# POVRotor.net
KiCad netlist of a schematic drawn in EAGLE
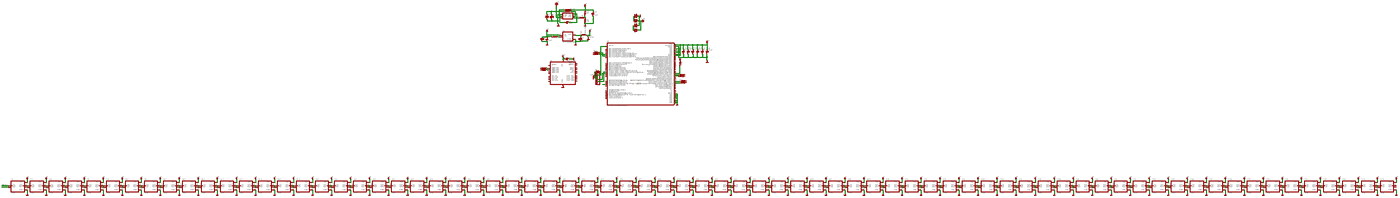
[diagram p0: schematic, sheet 1, overview]
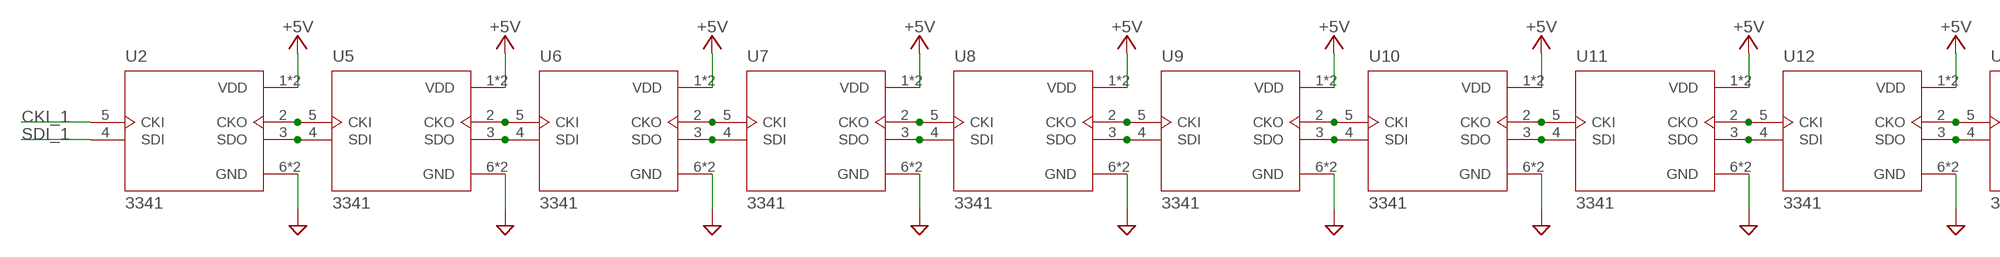
[diagram p1: schematic, sheet 1, part 1 of 8]
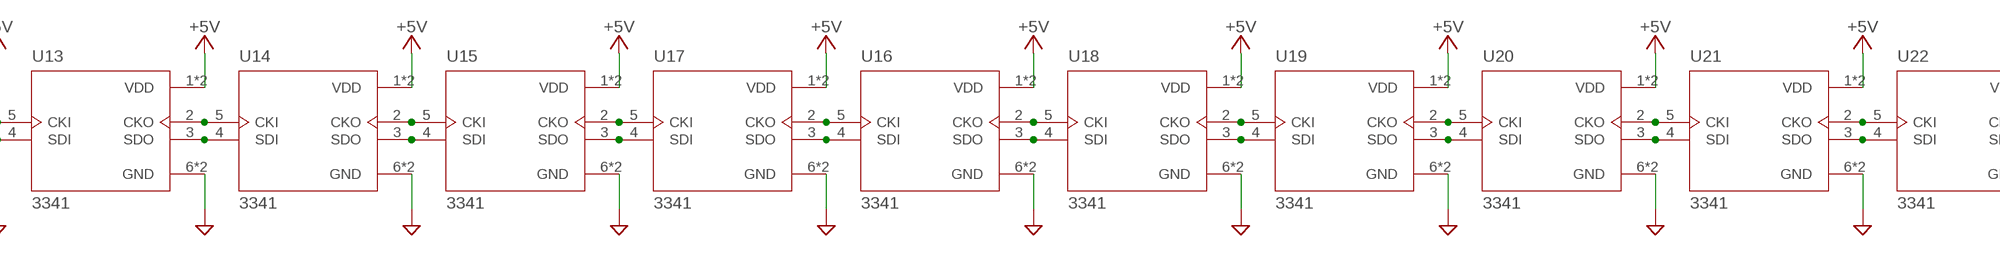
[diagram p2: schematic, sheet 1, part 2 of 8]
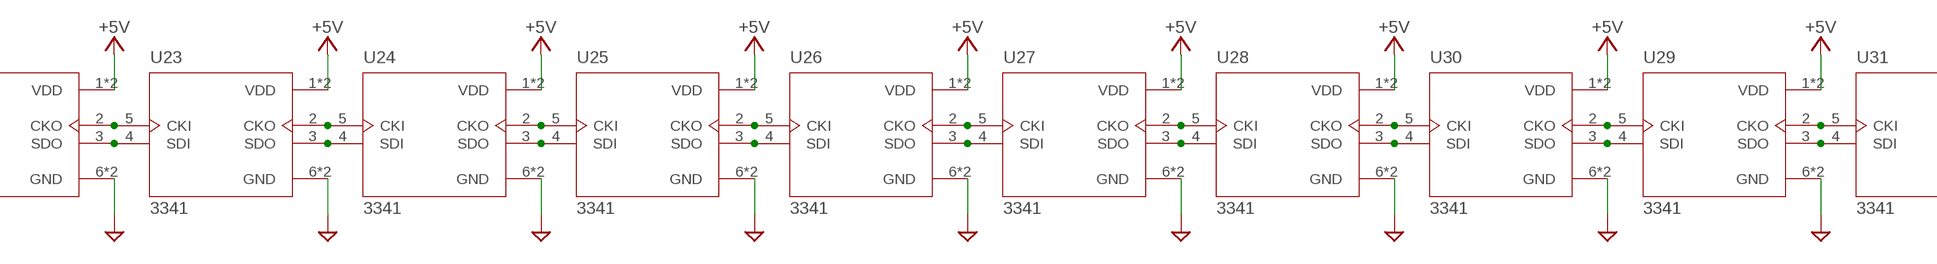
[diagram p3: schematic, sheet 1, part 3 of 8]
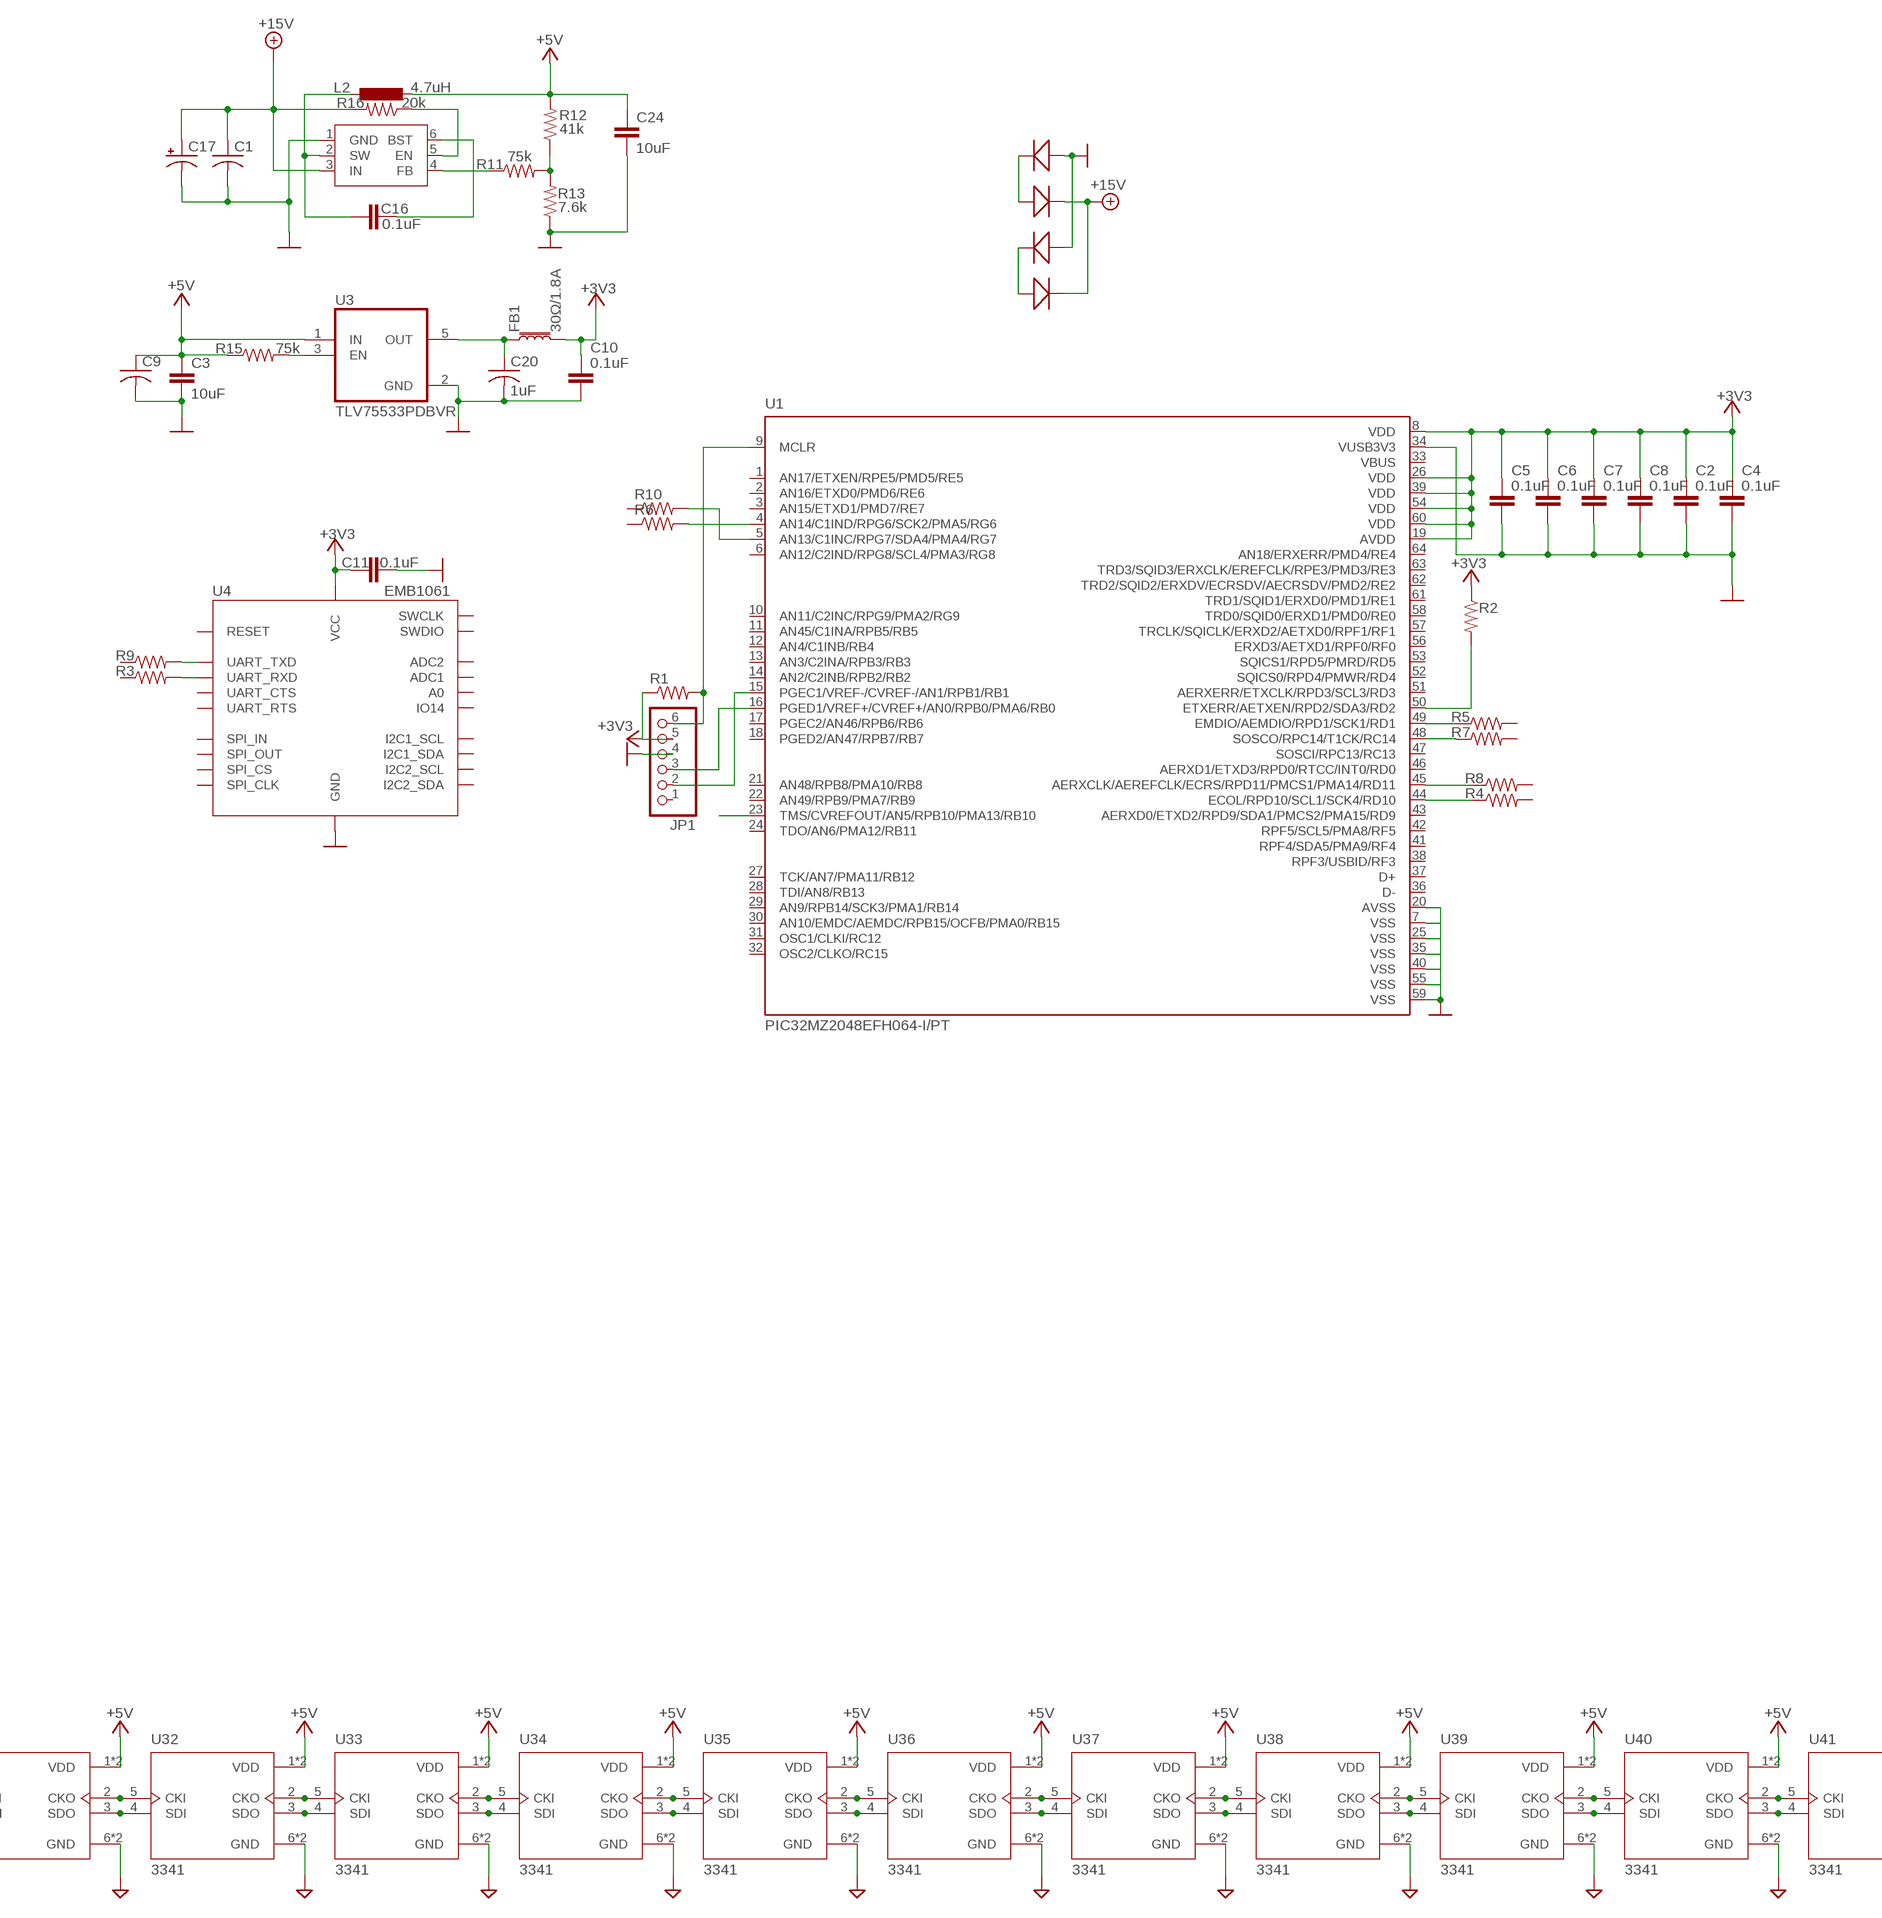
[diagram p4: schematic, sheet 1, part 4 of 8]
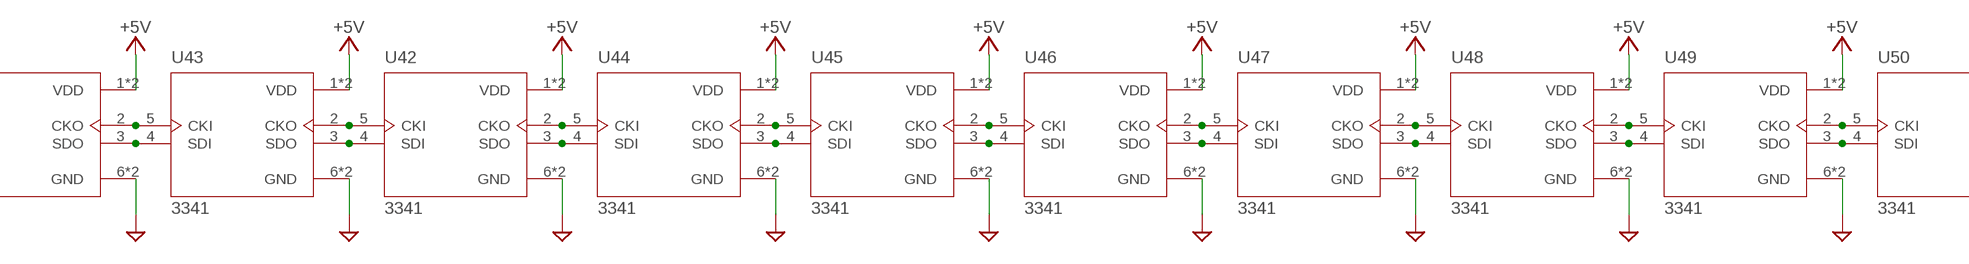
[diagram p5: schematic, sheet 1, part 5 of 8]
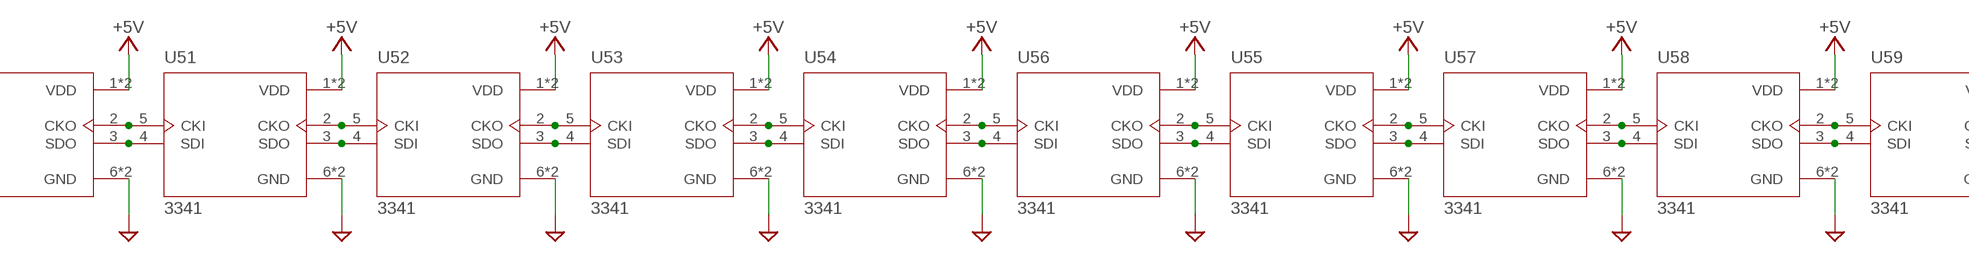
[diagram p6: schematic, sheet 1, part 6 of 8]
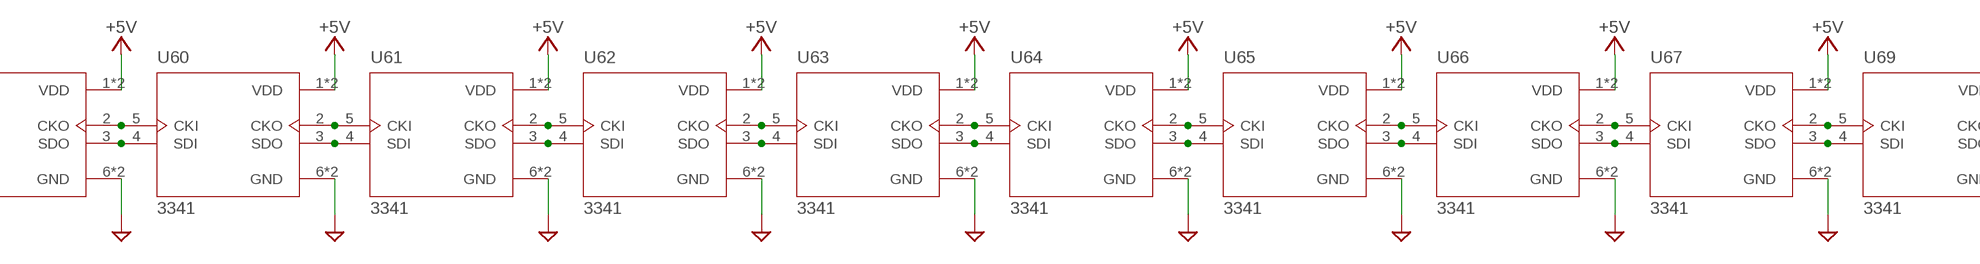
[diagram p7: schematic, sheet 1, part 7 of 8]
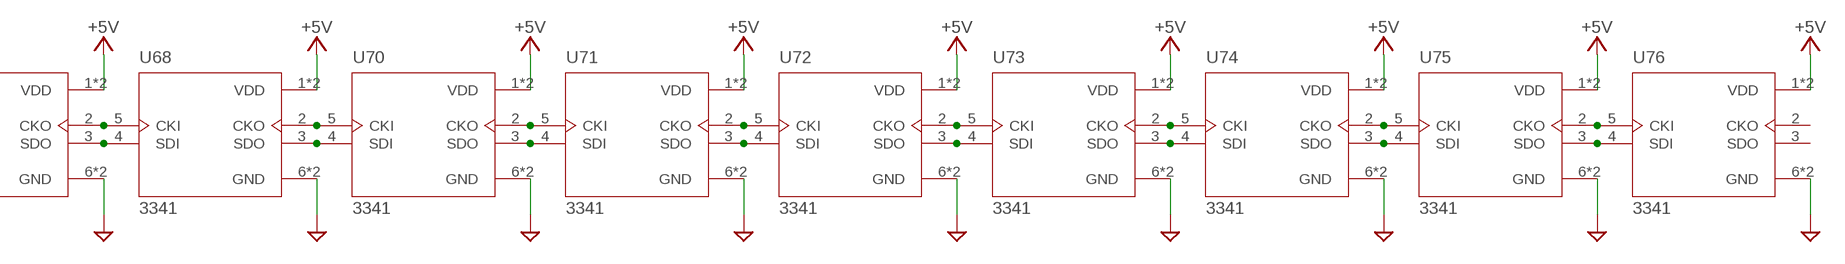
[diagram p8: schematic, sheet 1, part 8 of 8]

(export (version "E")
  (design (tool "Eeschema 10.0.6"))
  (components
    (comp (ref "C1")
      (value "C-USC0805")
      (footprint "eagle-import:C0805")
      (libsource (lib "eagle-import") (part "resistor_348_C-USC0805"))
    )
    (comp (ref "C2")
      (value "0.1uF")
      (footprint "eagle-import:C0603")
      (libsource (lib "eagle-import") (part "C-EUC0603"))
    )
    (comp (ref "C3")
      (value "10uF")
      (footprint "eagle-import:C1206")
      (libsource (lib "eagle-import") (part "C-EUC1206"))
    )
    (comp (ref "C4")
      (value "0.1uF")
      (footprint "eagle-import:C0603")
      (libsource (lib "eagle-import") (part "C-EUC0603"))
    )
    (comp (ref "C5")
      (value "0.1uF")
      (footprint "eagle-import:C0603")
      (libsource (lib "eagle-import") (part "C-EUC0603"))
    )
    (comp (ref "C6")
      (value "0.1uF")
      (footprint "eagle-import:C0603")
      (libsource (lib "eagle-import") (part "C-EUC0603"))
    )
    (comp (ref "C7")
      (value "0.1uF")
      (footprint "eagle-import:C0603")
      (libsource (lib "eagle-import") (part "C-EUC0603"))
    )
    (comp (ref "C8")
      (value "0.1uF")
      (footprint "eagle-import:C0603")
      (libsource (lib "eagle-import") (part "C-EUC0603"))
    )
    (comp (ref "C9")
      (value "C-USC0805")
      (footprint "eagle-import:C0805")
      (libsource (lib "eagle-import") (part "resistor_348_C-USC0805"))
    )
    (comp (ref "C10")
      (value "0.1uF")
      (footprint "eagle-import:C0603")
      (libsource (lib "eagle-import") (part "C-EUC0603"))
    )
    (comp (ref "C11")
      (value "0.1uF")
      (footprint "eagle-import:C0603")
      (libsource (lib "eagle-import") (part "C-EUC0603"))
    )
    (comp (ref "C16")
      (value "0.1uF")
      (footprint "eagle-import:C0603")
      (libsource (lib "eagle-import") (part "C-EUC0603"))
    )
    (comp (ref "C17")
      (value "CPOL-USC/6032-28R")
      (footprint "eagle-import:C_6032-28R")
      (libsource (lib "eagle-import") (part "CPOL-USC/6032-28R"))
    )
    (comp (ref "C20")
      (value "1uF")
      (footprint "eagle-import:C0805")
      (libsource (lib "eagle-import") (part "C-USC0805"))
    )
    (comp (ref "C24")
      (value "10uF")
      (footprint "eagle-import:C1206")
      (libsource (lib "eagle-import") (part "C-EUC1206"))
    )
    (comp (ref "D2")
      (value "SMD-DIODE-SCHOTTKY-40V-3A(DO-214AB)")
      (footprint "eagle-import:DO-214AB")
      (fields (field (name "MF") "Vishay") (field (name "MP") "SS34-E3/57T"))
      (libsource (lib "eagle-import") (part "SMD-DIODE-SCHOTTKY-40V-3A(DO-214AB)"))
    )
    (comp (ref "D3")
      (value "SMD-DIODE-SCHOTTKY-40V-3A(DO-214AB)")
      (footprint "eagle-import:DO-214AB")
      (fields (field (name "MF") "Vishay") (field (name "MP") "SS34-E3/57T"))
      (libsource (lib "eagle-import") (part "SMD-DIODE-SCHOTTKY-40V-3A(DO-214AB)"))
    )
    (comp (ref "D4")
      (value "SMD-DIODE-SCHOTTKY-40V-3A(DO-214AB)")
      (footprint "eagle-import:DO-214AB")
      (fields (field (name "MF") "Vishay") (field (name "MP") "SS34-E3/57T"))
      (libsource (lib "eagle-import") (part "SMD-DIODE-SCHOTTKY-40V-3A(DO-214AB)"))
    )
    (comp (ref "D5")
      (value "SMD-DIODE-SCHOTTKY-40V-3A(DO-214AB)")
      (footprint "eagle-import:DO-214AB")
      (fields (field (name "MF") "Vishay") (field (name "MP") "SS34-E3/57T"))
      (libsource (lib "eagle-import") (part "SMD-DIODE-SCHOTTKY-40V-3A(DO-214AB)"))
    )
    (comp (ref "FB1")
      (value "30Ω/1.8A")
      (footprint "eagle-import:0603")
      (libsource (lib "eagle-import") (part "FERRITE_BEAD-0603"))
    )
    (comp (ref "JP1")
      (value "PINHD-1X6/90")
      (footprint "eagle-import:1X06_90")
      (libsource (lib "eagle-import") (part "PINHD-1X6/90"))
    )
    (comp (ref "L2")
      (value "4.7uH")
      (footprint "eagle-import:L2825P")
      (libsource (lib "eagle-import") (part "L-EUL2825P"))
    )
    (comp (ref "R1")
      (value "R-US_R0603")
      (footprint "eagle-import:R0603")
      (libsource (lib "eagle-import") (part "resistor_348_R-US_R0603"))
    )
    (comp (ref "R2")
      (value "R-US_R0603")
      (footprint "eagle-import:R0603")
      (libsource (lib "eagle-import") (part "resistor_348_R-US_R0603"))
    )
    (comp (ref "R3")
      (value "R-US_R0603")
      (footprint "eagle-import:R0603")
      (libsource (lib "eagle-import") (part "resistor_348_R-US_R0603"))
    )
    (comp (ref "R4")
      (value "R-US_R0603")
      (footprint "eagle-import:R0603")
      (libsource (lib "eagle-import") (part "resistor_348_R-US_R0603"))
    )
    (comp (ref "R5")
      (value "R-US_R0603")
      (footprint "eagle-import:R0603")
      (libsource (lib "eagle-import") (part "resistor_348_R-US_R0603"))
    )
    (comp (ref "R6")
      (value "R-US_R0603")
      (footprint "eagle-import:R0603")
      (libsource (lib "eagle-import") (part "resistor_348_R-US_R0603"))
    )
    (comp (ref "R7")
      (value "R-US_R0603")
      (footprint "eagle-import:R0603")
      (libsource (lib "eagle-import") (part "resistor_348_R-US_R0603"))
    )
    (comp (ref "R8")
      (value "R-US_R0603")
      (footprint "eagle-import:R0603")
      (libsource (lib "eagle-import") (part "resistor_348_R-US_R0603"))
    )
    (comp (ref "R9")
      (value "R-US_R0603")
      (footprint "eagle-import:R0603")
      (libsource (lib "eagle-import") (part "resistor_348_R-US_R0603"))
    )
    (comp (ref "R10")
      (value "R-US_R0603")
      (footprint "eagle-import:R0603")
      (libsource (lib "eagle-import") (part "resistor_348_R-US_R0603"))
    )
    (comp (ref "R11")
      (value "75k")
      (footprint "eagle-import:R0603")
      (libsource (lib "eagle-import") (part "R-US_R0603"))
    )
    (comp (ref "R12")
      (value "41k")
      (footprint "eagle-import:R0603")
      (libsource (lib "eagle-import") (part "R-US_R0603"))
    )
    (comp (ref "R13")
      (value "7.6k")
      (footprint "eagle-import:R0603")
      (libsource (lib "eagle-import") (part "R-US_R0603"))
    )
    (comp (ref "R15")
      (value "75k")
      (footprint "eagle-import:R0603")
      (libsource (lib "eagle-import") (part "R-US_R0603"))
    )
    (comp (ref "R16")
      (value "20k")
      (footprint "eagle-import:R0603")
      (libsource (lib "eagle-import") (part "R-US_R0603"))
    )
    (comp (ref "U$74")
      (value "AP65211A")
      (footprint "eagle-import:SOT95P280X140-6N")
      (libsource (lib "eagle-import") (part "AP65211A"))
    )
    (comp (ref "U1")
      (value "PIC32MZ2048EFH064-I/PT")
      (footprint "eagle-import:QFP50P1200X1200X120-64N")
      (fields (field (name "MF") "Microchip"))
      (libsource (lib "eagle-import") (part "PIC32MZ2048EFH064-I/PT"))
    )
    (comp (ref "U2")
      (value "3341")
      (footprint "eagle-import:LED_3341")
      (fields (field (name "MF") "Adafruit Industries") (field (name "MP") "APA-102-2020-256-8"))
      (libsource (lib "eagle-import") (part "3341"))
    )
    (comp (ref "U3")
      (value "TLV75533PDBVR")
      (footprint "eagle-import:SOT95P280X145-5N")
      (fields (field (name "MF") "Texas Instruments"))
      (libsource (lib "eagle-import") (part "TLV75533PDBVR"))
    )
    (comp (ref "U4")
      (value "EMB1061")
      (footprint "eagle-import:EMB1061")
      (fields (field (name "MF") "U-Blox America") (field (name "MP") "SAM-M8Q"))
      (libsource (lib "eagle-import") (part "EMB1061"))
    )
    (comp (ref "U5")
      (value "3341")
      (footprint "eagle-import:LED_3341")
      (fields (field (name "MF") "Adafruit Industries") (field (name "MP") "APA-102-2020-256-8"))
      (libsource (lib "eagle-import") (part "3341"))
    )
    (comp (ref "U6")
      (value "3341")
      (footprint "eagle-import:LED_3341")
      (fields (field (name "MF") "Adafruit Industries") (field (name "MP") "APA-102-2020-256-8"))
      (libsource (lib "eagle-import") (part "3341"))
    )
    (comp (ref "U7")
      (value "3341")
      (footprint "eagle-import:LED_3341")
      (fields (field (name "MF") "Adafruit Industries") (field (name "MP") "APA-102-2020-256-8"))
      (libsource (lib "eagle-import") (part "3341"))
    )
    (comp (ref "U8")
      (value "3341")
      (footprint "eagle-import:LED_3341")
      (fields (field (name "MF") "Adafruit Industries") (field (name "MP") "APA-102-2020-256-8"))
      (libsource (lib "eagle-import") (part "3341"))
    )
    (comp (ref "U9")
      (value "3341")
      (footprint "eagle-import:LED_3341")
      (fields (field (name "MF") "Adafruit Industries") (field (name "MP") "APA-102-2020-256-8"))
      (libsource (lib "eagle-import") (part "3341"))
    )
    (comp (ref "U10")
      (value "3341")
      (footprint "eagle-import:LED_3341")
      (fields (field (name "MF") "Adafruit Industries") (field (name "MP") "APA-102-2020-256-8"))
      (libsource (lib "eagle-import") (part "3341"))
    )
    (comp (ref "U11")
      (value "3341")
      (footprint "eagle-import:LED_3341")
      (fields (field (name "MF") "Adafruit Industries") (field (name "MP") "APA-102-2020-256-8"))
      (libsource (lib "eagle-import") (part "3341"))
    )
    (comp (ref "U12")
      (value "3341")
      (footprint "eagle-import:LED_3341")
      (fields (field (name "MF") "Adafruit Industries") (field (name "MP") "APA-102-2020-256-8"))
      (libsource (lib "eagle-import") (part "3341"))
    )
    (comp (ref "U13")
      (value "3341")
      (footprint "eagle-import:LED_3341")
      (fields (field (name "MF") "Adafruit Industries") (field (name "MP") "APA-102-2020-256-8"))
      (libsource (lib "eagle-import") (part "3341"))
    )
    (comp (ref "U14")
      (value "3341")
      (footprint "eagle-import:LED_3341")
      (fields (field (name "MF") "Adafruit Industries") (field (name "MP") "APA-102-2020-256-8"))
      (libsource (lib "eagle-import") (part "3341"))
    )
    (comp (ref "U15")
      (value "3341")
      (footprint "eagle-import:LED_3341")
      (fields (field (name "MF") "Adafruit Industries") (field (name "MP") "APA-102-2020-256-8"))
      (libsource (lib "eagle-import") (part "3341"))
    )
    (comp (ref "U16")
      (value "3341")
      (footprint "eagle-import:LED_3341")
      (fields (field (name "MF") "Adafruit Industries") (field (name "MP") "APA-102-2020-256-8"))
      (libsource (lib "eagle-import") (part "3341"))
    )
    (comp (ref "U17")
      (value "3341")
      (footprint "eagle-import:LED_3341")
      (fields (field (name "MF") "Adafruit Industries") (field (name "MP") "APA-102-2020-256-8"))
      (libsource (lib "eagle-import") (part "3341"))
    )
    (comp (ref "U18")
      (value "3341")
      (footprint "eagle-import:LED_3341")
      (fields (field (name "MF") "Adafruit Industries") (field (name "MP") "APA-102-2020-256-8"))
      (libsource (lib "eagle-import") (part "3341"))
    )
    (comp (ref "U19")
      (value "3341")
      (footprint "eagle-import:LED_3341")
      (fields (field (name "MF") "Adafruit Industries") (field (name "MP") "APA-102-2020-256-8"))
      (libsource (lib "eagle-import") (part "3341"))
    )
    (comp (ref "U20")
      (value "3341")
      (footprint "eagle-import:LED_3341")
      (fields (field (name "MF") "Adafruit Industries") (field (name "MP") "APA-102-2020-256-8"))
      (libsource (lib "eagle-import") (part "3341"))
    )
    (comp (ref "U21")
      (value "3341")
      (footprint "eagle-import:LED_3341")
      (fields (field (name "MF") "Adafruit Industries") (field (name "MP") "APA-102-2020-256-8"))
      (libsource (lib "eagle-import") (part "3341"))
    )
    (comp (ref "U22")
      (value "3341")
      (footprint "eagle-import:LED_3341")
      (fields (field (name "MF") "Adafruit Industries") (field (name "MP") "APA-102-2020-256-8"))
      (libsource (lib "eagle-import") (part "3341"))
    )
    (comp (ref "U23")
      (value "3341")
      (footprint "eagle-import:LED_3341")
      (fields (field (name "MF") "Adafruit Industries") (field (name "MP") "APA-102-2020-256-8"))
      (libsource (lib "eagle-import") (part "3341"))
    )
    (comp (ref "U24")
      (value "3341")
      (footprint "eagle-import:LED_3341")
      (fields (field (name "MF") "Adafruit Industries") (field (name "MP") "APA-102-2020-256-8"))
      (libsource (lib "eagle-import") (part "3341"))
    )
    (comp (ref "U25")
      (value "3341")
      (footprint "eagle-import:LED_3341")
      (fields (field (name "MF") "Adafruit Industries") (field (name "MP") "APA-102-2020-256-8"))
      (libsource (lib "eagle-import") (part "3341"))
    )
    (comp (ref "U26")
      (value "3341")
      (footprint "eagle-import:LED_3341")
      (fields (field (name "MF") "Adafruit Industries") (field (name "MP") "APA-102-2020-256-8"))
      (libsource (lib "eagle-import") (part "3341"))
    )
    (comp (ref "U27")
      (value "3341")
      (footprint "eagle-import:LED_3341")
      (fields (field (name "MF") "Adafruit Industries") (field (name "MP") "APA-102-2020-256-8"))
      (libsource (lib "eagle-import") (part "3341"))
    )
    (comp (ref "U28")
      (value "3341")
      (footprint "eagle-import:LED_3341")
      (fields (field (name "MF") "Adafruit Industries") (field (name "MP") "APA-102-2020-256-8"))
      (libsource (lib "eagle-import") (part "3341"))
    )
    (comp (ref "U29")
      (value "3341")
      (footprint "eagle-import:LED_3341")
      (fields (field (name "MF") "Adafruit Industries") (field (name "MP") "APA-102-2020-256-8"))
      (libsource (lib "eagle-import") (part "3341"))
    )
    (comp (ref "U30")
      (value "3341")
      (footprint "eagle-import:LED_3341")
      (fields (field (name "MF") "Adafruit Industries") (field (name "MP") "APA-102-2020-256-8"))
      (libsource (lib "eagle-import") (part "3341"))
    )
    (comp (ref "U31")
      (value "3341")
      (footprint "eagle-import:LED_3341")
      (fields (field (name "MF") "Adafruit Industries") (field (name "MP") "APA-102-2020-256-8"))
      (libsource (lib "eagle-import") (part "3341"))
    )
    (comp (ref "U32")
      (value "3341")
      (footprint "eagle-import:LED_3341")
      (fields (field (name "MF") "Adafruit Industries") (field (name "MP") "APA-102-2020-256-8"))
      (libsource (lib "eagle-import") (part "3341"))
    )
    (comp (ref "U33")
      (value "3341")
      (footprint "eagle-import:LED_3341")
      (fields (field (name "MF") "Adafruit Industries") (field (name "MP") "APA-102-2020-256-8"))
      (libsource (lib "eagle-import") (part "3341"))
    )
    (comp (ref "U34")
      (value "3341")
      (footprint "eagle-import:LED_3341")
      (fields (field (name "MF") "Adafruit Industries") (field (name "MP") "APA-102-2020-256-8"))
      (libsource (lib "eagle-import") (part "3341"))
    )
    (comp (ref "U35")
      (value "3341")
      (footprint "eagle-import:LED_3341")
      (fields (field (name "MF") "Adafruit Industries") (field (name "MP") "APA-102-2020-256-8"))
      (libsource (lib "eagle-import") (part "3341"))
    )
    (comp (ref "U36")
      (value "3341")
      (footprint "eagle-import:LED_3341")
      (fields (field (name "MF") "Adafruit Industries") (field (name "MP") "APA-102-2020-256-8"))
      (libsource (lib "eagle-import") (part "3341"))
    )
    (comp (ref "U37")
      (value "3341")
      (footprint "eagle-import:LED_3341")
      (fields (field (name "MF") "Adafruit Industries") (field (name "MP") "APA-102-2020-256-8"))
      (libsource (lib "eagle-import") (part "3341"))
    )
    (comp (ref "U38")
      (value "3341")
      (footprint "eagle-import:LED_3341")
      (fields (field (name "MF") "Adafruit Industries") (field (name "MP") "APA-102-2020-256-8"))
      (libsource (lib "eagle-import") (part "3341"))
    )
    (comp (ref "U39")
      (value "3341")
      (footprint "eagle-import:LED_3341")
      (fields (field (name "MF") "Adafruit Industries") (field (name "MP") "APA-102-2020-256-8"))
      (libsource (lib "eagle-import") (part "3341"))
    )
    (comp (ref "U40")
      (value "3341")
      (footprint "eagle-import:LED_3341")
      (fields (field (name "MF") "Adafruit Industries") (field (name "MP") "APA-102-2020-256-8"))
      (libsource (lib "eagle-import") (part "3341"))
    )
    (comp (ref "U41")
      (value "3341")
      (footprint "eagle-import:LED_3341")
      (fields (field (name "MF") "Adafruit Industries") (field (name "MP") "APA-102-2020-256-8"))
      (libsource (lib "eagle-import") (part "3341"))
    )
    (comp (ref "U42")
      (value "3341")
      (footprint "eagle-import:LED_3341")
      (fields (field (name "MF") "Adafruit Industries") (field (name "MP") "APA-102-2020-256-8"))
      (libsource (lib "eagle-import") (part "3341"))
    )
    (comp (ref "U43")
      (value "3341")
      (footprint "eagle-import:LED_3341")
      (fields (field (name "MF") "Adafruit Industries") (field (name "MP") "APA-102-2020-256-8"))
      (libsource (lib "eagle-import") (part "3341"))
    )
    (comp (ref "U44")
      (value "3341")
      (footprint "eagle-import:LED_3341")
      (fields (field (name "MF") "Adafruit Industries") (field (name "MP") "APA-102-2020-256-8"))
      (libsource (lib "eagle-import") (part "3341"))
    )
    (comp (ref "U45")
      (value "3341")
      (footprint "eagle-import:LED_3341")
      (fields (field (name "MF") "Adafruit Industries") (field (name "MP") "APA-102-2020-256-8"))
      (libsource (lib "eagle-import") (part "3341"))
    )
    (comp (ref "U46")
      (value "3341")
      (footprint "eagle-import:LED_3341")
      (fields (field (name "MF") "Adafruit Industries") (field (name "MP") "APA-102-2020-256-8"))
      (libsource (lib "eagle-import") (part "3341"))
    )
    (comp (ref "U47")
      (value "3341")
      (footprint "eagle-import:LED_3341")
      (fields (field (name "MF") "Adafruit Industries") (field (name "MP") "APA-102-2020-256-8"))
      (libsource (lib "eagle-import") (part "3341"))
    )
    (comp (ref "U48")
      (value "3341")
      (footprint "eagle-import:LED_3341")
      (fields (field (name "MF") "Adafruit Industries") (field (name "MP") "APA-102-2020-256-8"))
      (libsource (lib "eagle-import") (part "3341"))
    )
    (comp (ref "U49")
      (value "3341")
      (footprint "eagle-import:LED_3341")
      (fields (field (name "MF") "Adafruit Industries") (field (name "MP") "APA-102-2020-256-8"))
      (libsource (lib "eagle-import") (part "3341"))
    )
    (comp (ref "U50")
      (value "3341")
      (footprint "eagle-import:LED_3341")
      (fields (field (name "MF") "Adafruit Industries") (field (name "MP") "APA-102-2020-256-8"))
      (libsource (lib "eagle-import") (part "3341"))
    )
    (comp (ref "U51")
      (value "3341")
      (footprint "eagle-import:LED_3341")
      (fields (field (name "MF") "Adafruit Industries") (field (name "MP") "APA-102-2020-256-8"))
      (libsource (lib "eagle-import") (part "3341"))
    )
    (comp (ref "U52")
      (value "3341")
      (footprint "eagle-import:LED_3341")
      (fields (field (name "MF") "Adafruit Industries") (field (name "MP") "APA-102-2020-256-8"))
      (libsource (lib "eagle-import") (part "3341"))
    )
    (comp (ref "U53")
      (value "3341")
      (footprint "eagle-import:LED_3341")
      (fields (field (name "MF") "Adafruit Industries") (field (name "MP") "APA-102-2020-256-8"))
      (libsource (lib "eagle-import") (part "3341"))
    )
    (comp (ref "U54")
      (value "3341")
      (footprint "eagle-import:LED_3341")
      (fields (field (name "MF") "Adafruit Industries") (field (name "MP") "APA-102-2020-256-8"))
      (libsource (lib "eagle-import") (part "3341"))
    )
    (comp (ref "U55")
      (value "3341")
      (footprint "eagle-import:LED_3341")
      (fields (field (name "MF") "Adafruit Industries") (field (name "MP") "APA-102-2020-256-8"))
      (libsource (lib "eagle-import") (part "3341"))
    )
    (comp (ref "U56")
      (value "3341")
      (footprint "eagle-import:LED_3341")
      (fields (field (name "MF") "Adafruit Industries") (field (name "MP") "APA-102-2020-256-8"))
      (libsource (lib "eagle-import") (part "3341"))
    )
    (comp (ref "U57")
      (value "3341")
      (footprint "eagle-import:LED_3341")
      (fields (field (name "MF") "Adafruit Industries") (field (name "MP") "APA-102-2020-256-8"))
      (libsource (lib "eagle-import") (part "3341"))
    )
    (comp (ref "U58")
      (value "3341")
      (footprint "eagle-import:LED_3341")
      (fields (field (name "MF") "Adafruit Industries") (field (name "MP") "APA-102-2020-256-8"))
      (libsource (lib "eagle-import") (part "3341"))
    )
    (comp (ref "U59")
      (value "3341")
      (footprint "eagle-import:LED_3341")
      (fields (field (name "MF") "Adafruit Industries") (field (name "MP") "APA-102-2020-256-8"))
      (libsource (lib "eagle-import") (part "3341"))
    )
    (comp (ref "U60")
      (value "3341")
      (footprint "eagle-import:LED_3341")
      (fields (field (name "MF") "Adafruit Industries") (field (name "MP") "APA-102-2020-256-8"))
      (libsource (lib "eagle-import") (part "3341"))
    )
    (comp (ref "U61")
      (value "3341")
      (footprint "eagle-import:LED_3341")
      (fields (field (name "MF") "Adafruit Industries") (field (name "MP") "APA-102-2020-256-8"))
      (libsource (lib "eagle-import") (part "3341"))
    )
    (comp (ref "U62")
      (value "3341")
      (footprint "eagle-import:LED_3341")
      (fields (field (name "MF") "Adafruit Industries") (field (name "MP") "APA-102-2020-256-8"))
      (libsource (lib "eagle-import") (part "3341"))
    )
    (comp (ref "U63")
      (value "3341")
      (footprint "eagle-import:LED_3341")
      (fields (field (name "MF") "Adafruit Industries") (field (name "MP") "APA-102-2020-256-8"))
      (libsource (lib "eagle-import") (part "3341"))
    )
    (comp (ref "U64")
      (value "3341")
      (footprint "eagle-import:LED_3341")
      (fields (field (name "MF") "Adafruit Industries") (field (name "MP") "APA-102-2020-256-8"))
      (libsource (lib "eagle-import") (part "3341"))
    )
    (comp (ref "U65")
      (value "3341")
      (footprint "eagle-import:LED_3341")
      (fields (field (name "MF") "Adafruit Industries") (field (name "MP") "APA-102-2020-256-8"))
      (libsource (lib "eagle-import") (part "3341"))
    )
    (comp (ref "U66")
      (value "3341")
      (footprint "eagle-import:LED_3341")
      (fields (field (name "MF") "Adafruit Industries") (field (name "MP") "APA-102-2020-256-8"))
      (libsource (lib "eagle-import") (part "3341"))
    )
    (comp (ref "U67")
      (value "3341")
      (footprint "eagle-import:LED_3341")
      (fields (field (name "MF") "Adafruit Industries") (field (name "MP") "APA-102-2020-256-8"))
      (libsource (lib "eagle-import") (part "3341"))
    )
    (comp (ref "U68")
      (value "3341")
      (footprint "eagle-import:LED_3341")
      (fields (field (name "MF") "Adafruit Industries") (field (name "MP") "APA-102-2020-256-8"))
      (libsource (lib "eagle-import") (part "3341"))
    )
    (comp (ref "U69")
      (value "3341")
      (footprint "eagle-import:LED_3341")
      (fields (field (name "MF") "Adafruit Industries") (field (name "MP") "APA-102-2020-256-8"))
      (libsource (lib "eagle-import") (part "3341"))
    )
    (comp (ref "U70")
      (value "3341")
      (footprint "eagle-import:LED_3341")
      (fields (field (name "MF") "Adafruit Industries") (field (name "MP") "APA-102-2020-256-8"))
      (libsource (lib "eagle-import") (part "3341"))
    )
    (comp (ref "U71")
      (value "3341")
      (footprint "eagle-import:LED_3341")
      (fields (field (name "MF") "Adafruit Industries") (field (name "MP") "APA-102-2020-256-8"))
      (libsource (lib "eagle-import") (part "3341"))
    )
    (comp (ref "U72")
      (value "3341")
      (footprint "eagle-import:LED_3341")
      (fields (field (name "MF") "Adafruit Industries") (field (name "MP") "APA-102-2020-256-8"))
      (libsource (lib "eagle-import") (part "3341"))
    )
    (comp (ref "U73")
      (value "3341")
      (footprint "eagle-import:LED_3341")
      (fields (field (name "MF") "Adafruit Industries") (field (name "MP") "APA-102-2020-256-8"))
      (libsource (lib "eagle-import") (part "3341"))
    )
    (comp (ref "U74")
      (value "3341")
      (footprint "eagle-import:LED_3341")
      (fields (field (name "MF") "Adafruit Industries") (field (name "MP") "APA-102-2020-256-8"))
      (libsource (lib "eagle-import") (part "3341"))
    )
    (comp (ref "U75")
      (value "3341")
      (footprint "eagle-import:LED_3341")
      (fields (field (name "MF") "Adafruit Industries") (field (name "MP") "APA-102-2020-256-8"))
      (libsource (lib "eagle-import") (part "3341"))
    )
    (comp (ref "U76")
      (value "3341")
      (footprint "eagle-import:LED_3341")
      (fields (field (name "MF") "Adafruit Industries") (field (name "MP") "APA-102-2020-256-8"))
      (libsource (lib "eagle-import") (part "3341"))
    )
  )
  (nets
    (net (code "1") (name "+3V3") (class "Default")
      (node (ref "C10") (pin "1") (pinfunction "1_1") (pintype "passive"))
      (node (ref "C11") (pin "1") (pinfunction "1_1") (pintype "passive"))
      (node (ref "C2") (pin "1") (pinfunction "1_1") (pintype "passive"))
      (node (ref "C4") (pin "1") (pinfunction "1_1") (pintype "passive"))
      (node (ref "C5") (pin "1") (pinfunction "1_1") (pintype "passive"))
      (node (ref "C6") (pin "1") (pinfunction "1_1") (pintype "passive"))
      (node (ref "C7") (pin "1") (pinfunction "1_1") (pintype "passive"))
      (node (ref "C8") (pin "1") (pinfunction "1_1") (pintype "passive"))
      (node (ref "FB1") (pin "2") (pinfunction "2_2") (pintype "passive"))
      (node (ref "JP1") (pin "5") (pinfunction "5_5") (pintype "passive"))
      (node (ref "R1") (pin "1") (pinfunction "1_1") (pintype "passive"))
      (node (ref "R2") (pin "1") (pinfunction "1_1") (pintype "passive"))
      (node (ref "U1") (pin "19") (pinfunction "AVDD_19") (pintype "power_in"))
      (node (ref "U1") (pin "26") (pinfunction "VDD_26") (pintype "power_in"))
      (node (ref "U1") (pin "39") (pinfunction "VDD_39") (pintype "power_in"))
      (node (ref "U1") (pin "54") (pinfunction "VDD_54") (pintype "power_in"))
      (node (ref "U1") (pin "60") (pinfunction "VDD_60") (pintype "power_in"))
      (node (ref "U1") (pin "8") (pinfunction "VDD_8") (pintype "power_in"))
      (node (ref "U4") (pin "P$8") (pinfunction "VCC_P$8") (pintype "bidirectional"))
    )
    (net (code "2") (name "+5V") (class "Default")
      (node (ref "C24") (pin "1") (pinfunction "1_1") (pintype "passive"))
      (node (ref "C3") (pin "1") (pinfunction "1_1") (pintype "passive"))
      (node (ref "C9") (pin "1") (pinfunction "1_1") (pintype "passive"))
      (node (ref "L2") (pin "1") (pinfunction "1_1") (pintype "passive"))
      (node (ref "R12") (pin "2") (pinfunction "2_2") (pintype "passive"))
      (node (ref "R15") (pin "1") (pinfunction "1_1") (pintype "passive"))
      (node (ref "U10") (pin "1") (pinfunction "VDD_1") (pintype "power_in"))
      (node (ref "U10") (pin "8") (pinfunction "VDD_8") (pintype "power_in"))
      (node (ref "U11") (pin "1") (pinfunction "VDD_1") (pintype "power_in"))
      (node (ref "U11") (pin "8") (pinfunction "VDD_8") (pintype "power_in"))
      (node (ref "U12") (pin "1") (pinfunction "VDD_1") (pintype "power_in"))
      (node (ref "U12") (pin "8") (pinfunction "VDD_8") (pintype "power_in"))
      (node (ref "U13") (pin "1") (pinfunction "VDD_1") (pintype "power_in"))
      (node (ref "U13") (pin "8") (pinfunction "VDD_8") (pintype "power_in"))
      (node (ref "U14") (pin "1") (pinfunction "VDD_1") (pintype "power_in"))
      (node (ref "U14") (pin "8") (pinfunction "VDD_8") (pintype "power_in"))
      (node (ref "U15") (pin "1") (pinfunction "VDD_1") (pintype "power_in"))
      (node (ref "U15") (pin "8") (pinfunction "VDD_8") (pintype "power_in"))
      (node (ref "U16") (pin "1") (pinfunction "VDD_1") (pintype "power_in"))
      (node (ref "U16") (pin "8") (pinfunction "VDD_8") (pintype "power_in"))
      (node (ref "U17") (pin "1") (pinfunction "VDD_1") (pintype "power_in"))
      (node (ref "U17") (pin "8") (pinfunction "VDD_8") (pintype "power_in"))
      (node (ref "U18") (pin "1") (pinfunction "VDD_1") (pintype "power_in"))
      (node (ref "U18") (pin "8") (pinfunction "VDD_8") (pintype "power_in"))
      (node (ref "U19") (pin "1") (pinfunction "VDD_1") (pintype "power_in"))
      (node (ref "U19") (pin "8") (pinfunction "VDD_8") (pintype "power_in"))
      (node (ref "U2") (pin "1") (pinfunction "VDD_1") (pintype "power_in"))
      (node (ref "U2") (pin "8") (pinfunction "VDD_8") (pintype "power_in"))
      (node (ref "U20") (pin "1") (pinfunction "VDD_1") (pintype "power_in"))
      (node (ref "U20") (pin "8") (pinfunction "VDD_8") (pintype "power_in"))
      (node (ref "U21") (pin "1") (pinfunction "VDD_1") (pintype "power_in"))
      (node (ref "U21") (pin "8") (pinfunction "VDD_8") (pintype "power_in"))
      (node (ref "U22") (pin "1") (pinfunction "VDD_1") (pintype "power_in"))
      (node (ref "U22") (pin "8") (pinfunction "VDD_8") (pintype "power_in"))
      (node (ref "U23") (pin "1") (pinfunction "VDD_1") (pintype "power_in"))
      (node (ref "U23") (pin "8") (pinfunction "VDD_8") (pintype "power_in"))
      (node (ref "U24") (pin "1") (pinfunction "VDD_1") (pintype "power_in"))
      (node (ref "U24") (pin "8") (pinfunction "VDD_8") (pintype "power_in"))
      (node (ref "U25") (pin "1") (pinfunction "VDD_1") (pintype "power_in"))
      (node (ref "U25") (pin "8") (pinfunction "VDD_8") (pintype "power_in"))
      (node (ref "U26") (pin "1") (pinfunction "VDD_1") (pintype "power_in"))
      (node (ref "U26") (pin "8") (pinfunction "VDD_8") (pintype "power_in"))
      (node (ref "U27") (pin "1") (pinfunction "VDD_1") (pintype "power_in"))
      (node (ref "U27") (pin "8") (pinfunction "VDD_8") (pintype "power_in"))
      (node (ref "U28") (pin "1") (pinfunction "VDD_1") (pintype "power_in"))
      (node (ref "U28") (pin "8") (pinfunction "VDD_8") (pintype "power_in"))
      (node (ref "U29") (pin "1") (pinfunction "VDD_1") (pintype "power_in"))
      (node (ref "U29") (pin "8") (pinfunction "VDD_8") (pintype "power_in"))
      (node (ref "U3") (pin "1") (pinfunction "IN_1") (pintype "input"))
      (node (ref "U30") (pin "1") (pinfunction "VDD_1") (pintype "power_in"))
      (node (ref "U30") (pin "8") (pinfunction "VDD_8") (pintype "power_in"))
      (node (ref "U31") (pin "1") (pinfunction "VDD_1") (pintype "power_in"))
      (node (ref "U31") (pin "8") (pinfunction "VDD_8") (pintype "power_in"))
      (node (ref "U32") (pin "1") (pinfunction "VDD_1") (pintype "power_in"))
      (node (ref "U32") (pin "8") (pinfunction "VDD_8") (pintype "power_in"))
      (node (ref "U33") (pin "1") (pinfunction "VDD_1") (pintype "power_in"))
      (node (ref "U33") (pin "8") (pinfunction "VDD_8") (pintype "power_in"))
      (node (ref "U34") (pin "1") (pinfunction "VDD_1") (pintype "power_in"))
      (node (ref "U34") (pin "8") (pinfunction "VDD_8") (pintype "power_in"))
      (node (ref "U35") (pin "1") (pinfunction "VDD_1") (pintype "power_in"))
      (node (ref "U35") (pin "8") (pinfunction "VDD_8") (pintype "power_in"))
      (node (ref "U36") (pin "1") (pinfunction "VDD_1") (pintype "power_in"))
      (node (ref "U36") (pin "8") (pinfunction "VDD_8") (pintype "power_in"))
      (node (ref "U37") (pin "1") (pinfunction "VDD_1") (pintype "power_in"))
      (node (ref "U37") (pin "8") (pinfunction "VDD_8") (pintype "power_in"))
      (node (ref "U38") (pin "1") (pinfunction "VDD_1") (pintype "power_in"))
      (node (ref "U38") (pin "8") (pinfunction "VDD_8") (pintype "power_in"))
      (node (ref "U39") (pin "1") (pinfunction "VDD_1") (pintype "power_in"))
      (node (ref "U39") (pin "8") (pinfunction "VDD_8") (pintype "power_in"))
      (node (ref "U40") (pin "1") (pinfunction "VDD_1") (pintype "power_in"))
      (node (ref "U40") (pin "8") (pinfunction "VDD_8") (pintype "power_in"))
      (node (ref "U41") (pin "1") (pinfunction "VDD_1") (pintype "power_in"))
      (node (ref "U41") (pin "8") (pinfunction "VDD_8") (pintype "power_in"))
      (node (ref "U42") (pin "1") (pinfunction "VDD_1") (pintype "power_in"))
      (node (ref "U42") (pin "8") (pinfunction "VDD_8") (pintype "power_in"))
      (node (ref "U43") (pin "1") (pinfunction "VDD_1") (pintype "power_in"))
      (node (ref "U43") (pin "8") (pinfunction "VDD_8") (pintype "power_in"))
      (node (ref "U44") (pin "1") (pinfunction "VDD_1") (pintype "power_in"))
      (node (ref "U44") (pin "8") (pinfunction "VDD_8") (pintype "power_in"))
      (node (ref "U45") (pin "1") (pinfunction "VDD_1") (pintype "power_in"))
      (node (ref "U45") (pin "8") (pinfunction "VDD_8") (pintype "power_in"))
      (node (ref "U46") (pin "1") (pinfunction "VDD_1") (pintype "power_in"))
      (node (ref "U46") (pin "8") (pinfunction "VDD_8") (pintype "power_in"))
      (node (ref "U47") (pin "1") (pinfunction "VDD_1") (pintype "power_in"))
      (node (ref "U47") (pin "8") (pinfunction "VDD_8") (pintype "power_in"))
      (node (ref "U48") (pin "1") (pinfunction "VDD_1") (pintype "power_in"))
      (node (ref "U48") (pin "8") (pinfunction "VDD_8") (pintype "power_in"))
      (node (ref "U49") (pin "1") (pinfunction "VDD_1") (pintype "power_in"))
      (node (ref "U49") (pin "8") (pinfunction "VDD_8") (pintype "power_in"))
      (node (ref "U5") (pin "1") (pinfunction "VDD_1") (pintype "power_in"))
      (node (ref "U5") (pin "8") (pinfunction "VDD_8") (pintype "power_in"))
      (node (ref "U50") (pin "1") (pinfunction "VDD_1") (pintype "power_in"))
      (node (ref "U50") (pin "8") (pinfunction "VDD_8") (pintype "power_in"))
      (node (ref "U51") (pin "1") (pinfunction "VDD_1") (pintype "power_in"))
      (node (ref "U51") (pin "8") (pinfunction "VDD_8") (pintype "power_in"))
      (node (ref "U52") (pin "1") (pinfunction "VDD_1") (pintype "power_in"))
      (node (ref "U52") (pin "8") (pinfunction "VDD_8") (pintype "power_in"))
      (node (ref "U53") (pin "1") (pinfunction "VDD_1") (pintype "power_in"))
      (node (ref "U53") (pin "8") (pinfunction "VDD_8") (pintype "power_in"))
      (node (ref "U54") (pin "1") (pinfunction "VDD_1") (pintype "power_in"))
      (node (ref "U54") (pin "8") (pinfunction "VDD_8") (pintype "power_in"))
      (node (ref "U55") (pin "1") (pinfunction "VDD_1") (pintype "power_in"))
      (node (ref "U55") (pin "8") (pinfunction "VDD_8") (pintype "power_in"))
      (node (ref "U56") (pin "1") (pinfunction "VDD_1") (pintype "power_in"))
      (node (ref "U56") (pin "8") (pinfunction "VDD_8") (pintype "power_in"))
      (node (ref "U57") (pin "1") (pinfunction "VDD_1") (pintype "power_in"))
      (node (ref "U57") (pin "8") (pinfunction "VDD_8") (pintype "power_in"))
      (node (ref "U58") (pin "1") (pinfunction "VDD_1") (pintype "power_in"))
      (node (ref "U58") (pin "8") (pinfunction "VDD_8") (pintype "power_in"))
      (node (ref "U59") (pin "1") (pinfunction "VDD_1") (pintype "power_in"))
      (node (ref "U59") (pin "8") (pinfunction "VDD_8") (pintype "power_in"))
      (node (ref "U6") (pin "1") (pinfunction "VDD_1") (pintype "power_in"))
      (node (ref "U6") (pin "8") (pinfunction "VDD_8") (pintype "power_in"))
      (node (ref "U60") (pin "1") (pinfunction "VDD_1") (pintype "power_in"))
      (node (ref "U60") (pin "8") (pinfunction "VDD_8") (pintype "power_in"))
      (node (ref "U61") (pin "1") (pinfunction "VDD_1") (pintype "power_in"))
      (node (ref "U61") (pin "8") (pinfunction "VDD_8") (pintype "power_in"))
      (node (ref "U62") (pin "1") (pinfunction "VDD_1") (pintype "power_in"))
      (node (ref "U62") (pin "8") (pinfunction "VDD_8") (pintype "power_in"))
      (node (ref "U63") (pin "1") (pinfunction "VDD_1") (pintype "power_in"))
      (node (ref "U63") (pin "8") (pinfunction "VDD_8") (pintype "power_in"))
      (node (ref "U64") (pin "1") (pinfunction "VDD_1") (pintype "power_in"))
      (node (ref "U64") (pin "8") (pinfunction "VDD_8") (pintype "power_in"))
      (node (ref "U65") (pin "1") (pinfunction "VDD_1") (pintype "power_in"))
      (node (ref "U65") (pin "8") (pinfunction "VDD_8") (pintype "power_in"))
      (node (ref "U66") (pin "1") (pinfunction "VDD_1") (pintype "power_in"))
      (node (ref "U66") (pin "8") (pinfunction "VDD_8") (pintype "power_in"))
      (node (ref "U67") (pin "1") (pinfunction "VDD_1") (pintype "power_in"))
      (node (ref "U67") (pin "8") (pinfunction "VDD_8") (pintype "power_in"))
      (node (ref "U68") (pin "1") (pinfunction "VDD_1") (pintype "power_in"))
      (node (ref "U68") (pin "8") (pinfunction "VDD_8") (pintype "power_in"))
      (node (ref "U69") (pin "1") (pinfunction "VDD_1") (pintype "power_in"))
      (node (ref "U69") (pin "8") (pinfunction "VDD_8") (pintype "power_in"))
      (node (ref "U7") (pin "1") (pinfunction "VDD_1") (pintype "power_in"))
      (node (ref "U7") (pin "8") (pinfunction "VDD_8") (pintype "power_in"))
      (node (ref "U70") (pin "1") (pinfunction "VDD_1") (pintype "power_in"))
      (node (ref "U70") (pin "8") (pinfunction "VDD_8") (pintype "power_in"))
      (node (ref "U71") (pin "1") (pinfunction "VDD_1") (pintype "power_in"))
      (node (ref "U71") (pin "8") (pinfunction "VDD_8") (pintype "power_in"))
      (node (ref "U72") (pin "1") (pinfunction "VDD_1") (pintype "power_in"))
      (node (ref "U72") (pin "8") (pinfunction "VDD_8") (pintype "power_in"))
      (node (ref "U73") (pin "1") (pinfunction "VDD_1") (pintype "power_in"))
      (node (ref "U73") (pin "8") (pinfunction "VDD_8") (pintype "power_in"))
      (node (ref "U74") (pin "1") (pinfunction "VDD_1") (pintype "power_in"))
      (node (ref "U74") (pin "8") (pinfunction "VDD_8") (pintype "power_in"))
      (node (ref "U75") (pin "1") (pinfunction "VDD_1") (pintype "power_in"))
      (node (ref "U75") (pin "8") (pinfunction "VDD_8") (pintype "power_in"))
      (node (ref "U76") (pin "1") (pinfunction "VDD_1") (pintype "power_in"))
      (node (ref "U76") (pin "8") (pinfunction "VDD_8") (pintype "power_in"))
      (node (ref "U8") (pin "1") (pinfunction "VDD_1") (pintype "power_in"))
      (node (ref "U8") (pin "8") (pinfunction "VDD_8") (pintype "power_in"))
      (node (ref "U9") (pin "1") (pinfunction "VDD_1") (pintype "power_in"))
      (node (ref "U9") (pin "8") (pinfunction "VDD_8") (pintype "power_in"))
    )
    (net (code "3") (name "+15V") (class "Default")
      (node (ref "C1") (pin "1") (pinfunction "1_1") (pintype "passive"))
      (node (ref "C17") (pin "+") (pinfunction "+_+") (pintype "passive"))
      (node (ref "D2") (pin "2") (pinfunction "-_2") (pintype "passive"))
      (node (ref "D3") (pin "2") (pinfunction "-_2") (pintype "passive"))
      (node (ref "R16") (pin "2") (pinfunction "2_2") (pintype "passive"))
      (node (ref "U$74") (pin "3") (pinfunction "IN_3") (pintype "bidirectional"))
    )
    (net (code "4") (name "/CKI_1") (class "Default")
      (node (ref "U2") (pin "5") (pinfunction "CKI_5") (pintype "input"))
    )
    (net (code "5") (name "/SDI_1") (class "Default")
      (node (ref "U2") (pin "4") (pinfunction "SDI_4") (pintype "input"))
    )
    (net (code "6") (name "/VBUS") (class "Default")
      (node (ref "U1") (pin "33") (pinfunction "VBUS_33") (pintype "power_in"))
    )
    (net (code "7") (name "GND") (class "Default")
      (node (ref "C1") (pin "2") (pinfunction "2_2") (pintype "passive"))
      (node (ref "C10") (pin "2") (pinfunction "2_2") (pintype "passive"))
      (node (ref "C11") (pin "2") (pinfunction "2_2") (pintype "passive"))
      (node (ref "C17") (pin "-") (pinfunction "-_-") (pintype "passive"))
      (node (ref "C2") (pin "2") (pinfunction "2_2") (pintype "passive"))
      (node (ref "C20") (pin "2") (pinfunction "2_2") (pintype "passive"))
      (node (ref "C24") (pin "2") (pinfunction "2_2") (pintype "passive"))
      (node (ref "C3") (pin "2") (pinfunction "2_2") (pintype "passive"))
      (node (ref "C4") (pin "2") (pinfunction "2_2") (pintype "passive"))
      (node (ref "C5") (pin "2") (pinfunction "2_2") (pintype "passive"))
      (node (ref "C6") (pin "2") (pinfunction "2_2") (pintype "passive"))
      (node (ref "C7") (pin "2") (pinfunction "2_2") (pintype "passive"))
      (node (ref "C8") (pin "2") (pinfunction "2_2") (pintype "passive"))
      (node (ref "C9") (pin "2") (pinfunction "2_2") (pintype "passive"))
      (node (ref "D4") (pin "1") (pinfunction "+_1") (pintype "passive"))
      (node (ref "D5") (pin "1") (pinfunction "+_1") (pintype "passive"))
      (node (ref "JP1") (pin "4") (pinfunction "4_4") (pintype "passive"))
      (node (ref "R13") (pin "1") (pinfunction "1_1") (pintype "passive"))
      (node (ref "U$74") (pin "1") (pinfunction "GND_1") (pintype "bidirectional"))
      (node (ref "U1") (pin "20") (pinfunction "AVSS_20") (pintype "power_in"))
      (node (ref "U1") (pin "25") (pinfunction "VSS_25") (pintype "power_in"))
      (node (ref "U1") (pin "34") (pinfunction "VUSB3V3_34") (pintype "power_in"))
      (node (ref "U1") (pin "35") (pinfunction "VSS_35") (pintype "power_in"))
      (node (ref "U1") (pin "40") (pinfunction "VSS_40") (pintype "power_in"))
      (node (ref "U1") (pin "55") (pinfunction "VSS_55") (pintype "power_in"))
      (node (ref "U1") (pin "59") (pinfunction "VSS_59") (pintype "power_in"))
      (node (ref "U1") (pin "7") (pinfunction "VSS_7") (pintype "power_in"))
      (node (ref "U10") (pin "6") (pinfunction "GND_6") (pintype "power_in"))
      (node (ref "U10") (pin "7") (pinfunction "GND_7") (pintype "power_in"))
      (node (ref "U11") (pin "6") (pinfunction "GND_6") (pintype "power_in"))
      (node (ref "U11") (pin "7") (pinfunction "GND_7") (pintype "power_in"))
      (node (ref "U12") (pin "6") (pinfunction "GND_6") (pintype "power_in"))
      (node (ref "U12") (pin "7") (pinfunction "GND_7") (pintype "power_in"))
      (node (ref "U13") (pin "6") (pinfunction "GND_6") (pintype "power_in"))
      (node (ref "U13") (pin "7") (pinfunction "GND_7") (pintype "power_in"))
      (node (ref "U14") (pin "6") (pinfunction "GND_6") (pintype "power_in"))
      (node (ref "U14") (pin "7") (pinfunction "GND_7") (pintype "power_in"))
      (node (ref "U15") (pin "6") (pinfunction "GND_6") (pintype "power_in"))
      (node (ref "U15") (pin "7") (pinfunction "GND_7") (pintype "power_in"))
      (node (ref "U16") (pin "6") (pinfunction "GND_6") (pintype "power_in"))
      (node (ref "U16") (pin "7") (pinfunction "GND_7") (pintype "power_in"))
      (node (ref "U17") (pin "6") (pinfunction "GND_6") (pintype "power_in"))
      (node (ref "U17") (pin "7") (pinfunction "GND_7") (pintype "power_in"))
      (node (ref "U18") (pin "6") (pinfunction "GND_6") (pintype "power_in"))
      (node (ref "U18") (pin "7") (pinfunction "GND_7") (pintype "power_in"))
      (node (ref "U19") (pin "6") (pinfunction "GND_6") (pintype "power_in"))
      (node (ref "U19") (pin "7") (pinfunction "GND_7") (pintype "power_in"))
      (node (ref "U2") (pin "6") (pinfunction "GND_6") (pintype "power_in"))
      (node (ref "U2") (pin "7") (pinfunction "GND_7") (pintype "power_in"))
      (node (ref "U20") (pin "6") (pinfunction "GND_6") (pintype "power_in"))
      (node (ref "U20") (pin "7") (pinfunction "GND_7") (pintype "power_in"))
      (node (ref "U21") (pin "6") (pinfunction "GND_6") (pintype "power_in"))
      (node (ref "U21") (pin "7") (pinfunction "GND_7") (pintype "power_in"))
      (node (ref "U22") (pin "6") (pinfunction "GND_6") (pintype "power_in"))
      (node (ref "U22") (pin "7") (pinfunction "GND_7") (pintype "power_in"))
      (node (ref "U23") (pin "6") (pinfunction "GND_6") (pintype "power_in"))
      (node (ref "U23") (pin "7") (pinfunction "GND_7") (pintype "power_in"))
      (node (ref "U24") (pin "6") (pinfunction "GND_6") (pintype "power_in"))
      (node (ref "U24") (pin "7") (pinfunction "GND_7") (pintype "power_in"))
      (node (ref "U25") (pin "6") (pinfunction "GND_6") (pintype "power_in"))
      (node (ref "U25") (pin "7") (pinfunction "GND_7") (pintype "power_in"))
      (node (ref "U26") (pin "6") (pinfunction "GND_6") (pintype "power_in"))
      (node (ref "U26") (pin "7") (pinfunction "GND_7") (pintype "power_in"))
      (node (ref "U27") (pin "6") (pinfunction "GND_6") (pintype "power_in"))
      (node (ref "U27") (pin "7") (pinfunction "GND_7") (pintype "power_in"))
      (node (ref "U28") (pin "6") (pinfunction "GND_6") (pintype "power_in"))
      (node (ref "U28") (pin "7") (pinfunction "GND_7") (pintype "power_in"))
      (node (ref "U29") (pin "6") (pinfunction "GND_6") (pintype "power_in"))
      (node (ref "U29") (pin "7") (pinfunction "GND_7") (pintype "power_in"))
      (node (ref "U3") (pin "2") (pinfunction "GND_2") (pintype "power_in"))
      (node (ref "U30") (pin "6") (pinfunction "GND_6") (pintype "power_in"))
      (node (ref "U30") (pin "7") (pinfunction "GND_7") (pintype "power_in"))
      (node (ref "U31") (pin "6") (pinfunction "GND_6") (pintype "power_in"))
      (node (ref "U31") (pin "7") (pinfunction "GND_7") (pintype "power_in"))
      (node (ref "U32") (pin "6") (pinfunction "GND_6") (pintype "power_in"))
      (node (ref "U32") (pin "7") (pinfunction "GND_7") (pintype "power_in"))
      (node (ref "U33") (pin "6") (pinfunction "GND_6") (pintype "power_in"))
      (node (ref "U33") (pin "7") (pinfunction "GND_7") (pintype "power_in"))
      (node (ref "U34") (pin "6") (pinfunction "GND_6") (pintype "power_in"))
      (node (ref "U34") (pin "7") (pinfunction "GND_7") (pintype "power_in"))
      (node (ref "U35") (pin "6") (pinfunction "GND_6") (pintype "power_in"))
      (node (ref "U35") (pin "7") (pinfunction "GND_7") (pintype "power_in"))
      (node (ref "U36") (pin "6") (pinfunction "GND_6") (pintype "power_in"))
      (node (ref "U36") (pin "7") (pinfunction "GND_7") (pintype "power_in"))
      (node (ref "U37") (pin "6") (pinfunction "GND_6") (pintype "power_in"))
      (node (ref "U37") (pin "7") (pinfunction "GND_7") (pintype "power_in"))
      (node (ref "U38") (pin "6") (pinfunction "GND_6") (pintype "power_in"))
      (node (ref "U38") (pin "7") (pinfunction "GND_7") (pintype "power_in"))
      (node (ref "U39") (pin "6") (pinfunction "GND_6") (pintype "power_in"))
      (node (ref "U39") (pin "7") (pinfunction "GND_7") (pintype "power_in"))
      (node (ref "U4") (pin "P$22") (pinfunction "GND_P$22") (pintype "bidirectional"))
      (node (ref "U4") (pin "P$9") (pinfunction "GND_P$9") (pintype "bidirectional"))
      (node (ref "U40") (pin "6") (pinfunction "GND_6") (pintype "power_in"))
      (node (ref "U40") (pin "7") (pinfunction "GND_7") (pintype "power_in"))
      (node (ref "U41") (pin "6") (pinfunction "GND_6") (pintype "power_in"))
      (node (ref "U41") (pin "7") (pinfunction "GND_7") (pintype "power_in"))
      (node (ref "U42") (pin "6") (pinfunction "GND_6") (pintype "power_in"))
      (node (ref "U42") (pin "7") (pinfunction "GND_7") (pintype "power_in"))
      (node (ref "U43") (pin "6") (pinfunction "GND_6") (pintype "power_in"))
      (node (ref "U43") (pin "7") (pinfunction "GND_7") (pintype "power_in"))
      (node (ref "U44") (pin "6") (pinfunction "GND_6") (pintype "power_in"))
      (node (ref "U44") (pin "7") (pinfunction "GND_7") (pintype "power_in"))
      (node (ref "U45") (pin "6") (pinfunction "GND_6") (pintype "power_in"))
      (node (ref "U45") (pin "7") (pinfunction "GND_7") (pintype "power_in"))
      (node (ref "U46") (pin "6") (pinfunction "GND_6") (pintype "power_in"))
      (node (ref "U46") (pin "7") (pinfunction "GND_7") (pintype "power_in"))
      (node (ref "U47") (pin "6") (pinfunction "GND_6") (pintype "power_in"))
      (node (ref "U47") (pin "7") (pinfunction "GND_7") (pintype "power_in"))
      (node (ref "U48") (pin "6") (pinfunction "GND_6") (pintype "power_in"))
      (node (ref "U48") (pin "7") (pinfunction "GND_7") (pintype "power_in"))
      (node (ref "U49") (pin "6") (pinfunction "GND_6") (pintype "power_in"))
      (node (ref "U49") (pin "7") (pinfunction "GND_7") (pintype "power_in"))
      (node (ref "U5") (pin "6") (pinfunction "GND_6") (pintype "power_in"))
      (node (ref "U5") (pin "7") (pinfunction "GND_7") (pintype "power_in"))
      (node (ref "U50") (pin "6") (pinfunction "GND_6") (pintype "power_in"))
      (node (ref "U50") (pin "7") (pinfunction "GND_7") (pintype "power_in"))
      (node (ref "U51") (pin "6") (pinfunction "GND_6") (pintype "power_in"))
      (node (ref "U51") (pin "7") (pinfunction "GND_7") (pintype "power_in"))
      (node (ref "U52") (pin "6") (pinfunction "GND_6") (pintype "power_in"))
      (node (ref "U52") (pin "7") (pinfunction "GND_7") (pintype "power_in"))
      (node (ref "U53") (pin "6") (pinfunction "GND_6") (pintype "power_in"))
      (node (ref "U53") (pin "7") (pinfunction "GND_7") (pintype "power_in"))
      (node (ref "U54") (pin "6") (pinfunction "GND_6") (pintype "power_in"))
      (node (ref "U54") (pin "7") (pinfunction "GND_7") (pintype "power_in"))
      (node (ref "U55") (pin "6") (pinfunction "GND_6") (pintype "power_in"))
      (node (ref "U55") (pin "7") (pinfunction "GND_7") (pintype "power_in"))
      (node (ref "U56") (pin "6") (pinfunction "GND_6") (pintype "power_in"))
      (node (ref "U56") (pin "7") (pinfunction "GND_7") (pintype "power_in"))
      (node (ref "U57") (pin "6") (pinfunction "GND_6") (pintype "power_in"))
      (node (ref "U57") (pin "7") (pinfunction "GND_7") (pintype "power_in"))
      (node (ref "U58") (pin "6") (pinfunction "GND_6") (pintype "power_in"))
      (node (ref "U58") (pin "7") (pinfunction "GND_7") (pintype "power_in"))
      (node (ref "U59") (pin "6") (pinfunction "GND_6") (pintype "power_in"))
      (node (ref "U59") (pin "7") (pinfunction "GND_7") (pintype "power_in"))
      (node (ref "U6") (pin "6") (pinfunction "GND_6") (pintype "power_in"))
      (node (ref "U6") (pin "7") (pinfunction "GND_7") (pintype "power_in"))
      (node (ref "U60") (pin "6") (pinfunction "GND_6") (pintype "power_in"))
      (node (ref "U60") (pin "7") (pinfunction "GND_7") (pintype "power_in"))
      (node (ref "U61") (pin "6") (pinfunction "GND_6") (pintype "power_in"))
      (node (ref "U61") (pin "7") (pinfunction "GND_7") (pintype "power_in"))
      (node (ref "U62") (pin "6") (pinfunction "GND_6") (pintype "power_in"))
      (node (ref "U62") (pin "7") (pinfunction "GND_7") (pintype "power_in"))
      (node (ref "U63") (pin "6") (pinfunction "GND_6") (pintype "power_in"))
      (node (ref "U63") (pin "7") (pinfunction "GND_7") (pintype "power_in"))
      (node (ref "U64") (pin "6") (pinfunction "GND_6") (pintype "power_in"))
      (node (ref "U64") (pin "7") (pinfunction "GND_7") (pintype "power_in"))
      (node (ref "U65") (pin "6") (pinfunction "GND_6") (pintype "power_in"))
      (node (ref "U65") (pin "7") (pinfunction "GND_7") (pintype "power_in"))
      (node (ref "U66") (pin "6") (pinfunction "GND_6") (pintype "power_in"))
      (node (ref "U66") (pin "7") (pinfunction "GND_7") (pintype "power_in"))
      (node (ref "U67") (pin "6") (pinfunction "GND_6") (pintype "power_in"))
      (node (ref "U67") (pin "7") (pinfunction "GND_7") (pintype "power_in"))
      (node (ref "U68") (pin "6") (pinfunction "GND_6") (pintype "power_in"))
      (node (ref "U68") (pin "7") (pinfunction "GND_7") (pintype "power_in"))
      (node (ref "U69") (pin "6") (pinfunction "GND_6") (pintype "power_in"))
      (node (ref "U69") (pin "7") (pinfunction "GND_7") (pintype "power_in"))
      (node (ref "U7") (pin "6") (pinfunction "GND_6") (pintype "power_in"))
      (node (ref "U7") (pin "7") (pinfunction "GND_7") (pintype "power_in"))
      (node (ref "U70") (pin "6") (pinfunction "GND_6") (pintype "power_in"))
      (node (ref "U70") (pin "7") (pinfunction "GND_7") (pintype "power_in"))
      (node (ref "U71") (pin "6") (pinfunction "GND_6") (pintype "power_in"))
      (node (ref "U71") (pin "7") (pinfunction "GND_7") (pintype "power_in"))
      (node (ref "U72") (pin "6") (pinfunction "GND_6") (pintype "power_in"))
      (node (ref "U72") (pin "7") (pinfunction "GND_7") (pintype "power_in"))
      (node (ref "U73") (pin "6") (pinfunction "GND_6") (pintype "power_in"))
      (node (ref "U73") (pin "7") (pinfunction "GND_7") (pintype "power_in"))
      (node (ref "U74") (pin "6") (pinfunction "GND_6") (pintype "power_in"))
      (node (ref "U74") (pin "7") (pinfunction "GND_7") (pintype "power_in"))
      (node (ref "U75") (pin "6") (pinfunction "GND_6") (pintype "power_in"))
      (node (ref "U75") (pin "7") (pinfunction "GND_7") (pintype "power_in"))
      (node (ref "U76") (pin "6") (pinfunction "GND_6") (pintype "power_in"))
      (node (ref "U76") (pin "7") (pinfunction "GND_7") (pintype "power_in"))
      (node (ref "U8") (pin "6") (pinfunction "GND_6") (pintype "power_in"))
      (node (ref "U8") (pin "7") (pinfunction "GND_7") (pintype "power_in"))
      (node (ref "U9") (pin "6") (pinfunction "GND_6") (pintype "power_in"))
      (node (ref "U9") (pin "7") (pinfunction "GND_7") (pintype "power_in"))
    )
    (net (code "8") (name "Net-(D2-+)") (class "Default")
      (node (ref "D2") (pin "1") (pinfunction "+_1") (pintype "passive"))
      (node (ref "D5") (pin "2") (pinfunction "-_2") (pintype "passive"))
    )
    (net (code "9") (name "Net-(D3-+)") (class "Default")
      (node (ref "D3") (pin "1") (pinfunction "+_1") (pintype "passive"))
      (node (ref "D4") (pin "2") (pinfunction "-_2") (pintype "passive"))
    )
    (net (code "10") (name "Net-(R11-Pad2)") (class "Default")
      (node (ref "R11") (pin "2") (pinfunction "2_2") (pintype "passive"))
      (node (ref "R12") (pin "1") (pinfunction "1_1") (pintype "passive"))
      (node (ref "R13") (pin "2") (pinfunction "2_2") (pintype "passive"))
    )
    (net (code "11") (name "Net-(U$74-BST)") (class "Default")
      (node (ref "C16") (pin "2") (pinfunction "2_2") (pintype "passive"))
      (node (ref "U$74") (pin "6") (pinfunction "BST_6") (pintype "bidirectional"))
    )
    (net (code "12") (name "Net-(U$74-EN)") (class "Default")
      (node (ref "R16") (pin "1") (pinfunction "1_1") (pintype "passive"))
      (node (ref "U$74") (pin "5") (pinfunction "EN_5") (pintype "bidirectional"))
    )
    (net (code "13") (name "Net-(U$74-FB)") (class "Default")
      (node (ref "R11") (pin "1") (pinfunction "1_1") (pintype "passive"))
      (node (ref "U$74") (pin "4") (pinfunction "FB_4") (pintype "bidirectional"))
    )
    (net (code "14") (name "Net-(U$74-SW)") (class "Default")
      (node (ref "C16") (pin "1") (pinfunction "1_1") (pintype "passive"))
      (node (ref "L2") (pin "2") (pinfunction "2_2") (pintype "passive"))
      (node (ref "U$74") (pin "2") (pinfunction "SW_2") (pintype "bidirectional"))
    )
    (net (code "15") (name "Net-(U1-AERXCLK{slash}AEREFCLK{slash}ECRS{slash}RPD11{slash}PMCS1{slash}PMA14{slash}RD11)") (class "Default")
      (node (ref "R8") (pin "1") (pinfunction "1_1") (pintype "passive"))
      (node (ref "U1") (pin "45") (pinfunction "AERXCLK/AEREFCLK/ECRS/RPD11/PMCS1/PMA14/RD11_45") (pintype "bidirectional"))
    )
    (net (code "16") (name "Net-(U1-AN13{slash}C1INC{slash}RPG7{slash}SDA4{slash}PMA4{slash}RG7)") (class "Default")
      (node (ref "R10") (pin "2") (pinfunction "2_2") (pintype "passive"))
      (node (ref "U1") (pin "5") (pinfunction "AN13/C1INC/RPG7/SDA4/PMA4/RG7_5") (pintype "bidirectional"))
    )
    (net (code "17") (name "Net-(U1-AN14{slash}C1IND{slash}RPG6{slash}SCK2{slash}PMA5{slash}RG6)") (class "Default")
      (node (ref "R6") (pin "2") (pinfunction "2_2") (pintype "passive"))
      (node (ref "U1") (pin "4") (pinfunction "AN14/C1IND/RPG6/SCK2/PMA5/RG6_4") (pintype "bidirectional"))
    )
    (net (code "18") (name "Net-(U1-ECOL{slash}RPD10{slash}SCL1{slash}SCK4{slash}RD10)") (class "Default")
      (node (ref "R4") (pin "1") (pinfunction "1_1") (pintype "passive"))
      (node (ref "U1") (pin "44") (pinfunction "ECOL/RPD10/SCL1/SCK4/RD10_44") (pintype "bidirectional"))
    )
    (net (code "19") (name "Net-(U1-EMDIO{slash}AEMDIO{slash}RPD1{slash}SCK1{slash}RD1)") (class "Default")
      (node (ref "R5") (pin "1") (pinfunction "1_1") (pintype "passive"))
      (node (ref "U1") (pin "49") (pinfunction "EMDIO/AEMDIO/RPD1/SCK1/RD1_49") (pintype "bidirectional"))
    )
    (net (code "20") (name "Net-(U1-ETXERR{slash}AETXEN{slash}RPD2{slash}SDA3{slash}RD2)") (class "Default")
      (node (ref "R2") (pin "2") (pinfunction "2_2") (pintype "passive"))
      (node (ref "U1") (pin "50") (pinfunction "ETXERR/AETXEN/RPD2/SDA3/RD2_50") (pintype "bidirectional"))
    )
    (net (code "21") (name "Net-(U1-MCLR)") (class "Default")
      (node (ref "JP1") (pin "6") (pinfunction "6_6") (pintype "passive"))
      (node (ref "R1") (pin "2") (pinfunction "2_2") (pintype "passive"))
      (node (ref "U1") (pin "9") (pinfunction "MCLR_9") (pintype "input"))
    )
    (net (code "22") (name "Net-(U1-PGEC1{slash}VREF-{slash}CVREF-{slash}AN1{slash}RPB1{slash}RB1)") (class "Default")
      (node (ref "JP1") (pin "2") (pinfunction "2_2") (pintype "passive"))
      (node (ref "U1") (pin "15") (pinfunction "PGEC1/VREF-/CVREF-/AN1/RPB1/RB1_15") (pintype "bidirectional"))
    )
    (net (code "23") (name "Net-(U1-PGED1{slash}VREF+{slash}CVREF+{slash}AN0{slash}RPB0{slash}PMA6{slash}RB0)") (class "Default")
      (node (ref "JP1") (pin "3") (pinfunction "3_3") (pintype "passive"))
      (node (ref "U1") (pin "16") (pinfunction "PGED1/VREF+/CVREF+/AN0/RPB0/PMA6/RB0_16") (pintype "bidirectional"))
    )
    (net (code "24") (name "Net-(U1-SOSCO{slash}RPC14{slash}T1CK{slash}RC14)") (class "Default")
      (node (ref "R7") (pin "1") (pinfunction "1_1") (pintype "passive"))
      (node (ref "U1") (pin "48") (pinfunction "SOSCO/RPC14/T1CK/RC14_48") (pintype "bidirectional"))
    )
    (net (code "25") (name "Net-(U2-CKO)") (class "Default")
      (node (ref "U2") (pin "2") (pinfunction "CKO_2") (pintype "output"))
      (node (ref "U5") (pin "5") (pinfunction "CKI_5") (pintype "input"))
    )
    (net (code "26") (name "Net-(U2-SDO)") (class "Default")
      (node (ref "U2") (pin "3") (pinfunction "SDO_3") (pintype "output"))
      (node (ref "U5") (pin "4") (pinfunction "SDI_4") (pintype "input"))
    )
    (net (code "27") (name "Net-(U3-EN)") (class "Default")
      (node (ref "R15") (pin "2") (pinfunction "2_2") (pintype "passive"))
      (node (ref "U3") (pin "3") (pinfunction "EN_3") (pintype "input"))
    )
    (net (code "28") (name "Net-(U3-OUT)") (class "Default")
      (node (ref "C20") (pin "1") (pinfunction "1_1") (pintype "passive"))
      (node (ref "FB1") (pin "1") (pinfunction "1_1") (pintype "passive"))
      (node (ref "U3") (pin "5") (pinfunction "OUT_5") (pintype "output"))
    )
    (net (code "29") (name "Net-(U4-UART_RXD)") (class "Default")
      (node (ref "R3") (pin "2") (pinfunction "2_2") (pintype "passive"))
      (node (ref "U4") (pin "P$11") (pinfunction "UART_RXD_P$11") (pintype "bidirectional"))
    )
    (net (code "30") (name "Net-(U4-UART_TXD)") (class "Default")
      (node (ref "R9") (pin "2") (pinfunction "2_2") (pintype "passive"))
      (node (ref "U4") (pin "P$10") (pinfunction "UART_TXD_P$10") (pintype "bidirectional"))
    )
    (net (code "31") (name "Net-(U5-CKO)") (class "Default")
      (node (ref "U5") (pin "2") (pinfunction "CKO_2") (pintype "output"))
      (node (ref "U6") (pin "5") (pinfunction "CKI_5") (pintype "input"))
    )
    (net (code "32") (name "Net-(U5-SDO)") (class "Default")
      (node (ref "U5") (pin "3") (pinfunction "SDO_3") (pintype "output"))
      (node (ref "U6") (pin "4") (pinfunction "SDI_4") (pintype "input"))
    )
    (net (code "33") (name "Net-(U6-CKO)") (class "Default")
      (node (ref "U6") (pin "2") (pinfunction "CKO_2") (pintype "output"))
      (node (ref "U7") (pin "5") (pinfunction "CKI_5") (pintype "input"))
    )
    (net (code "34") (name "Net-(U6-SDO)") (class "Default")
      (node (ref "U6") (pin "3") (pinfunction "SDO_3") (pintype "output"))
      (node (ref "U7") (pin "4") (pinfunction "SDI_4") (pintype "input"))
    )
    (net (code "35") (name "Net-(U7-CKO)") (class "Default")
      (node (ref "U7") (pin "2") (pinfunction "CKO_2") (pintype "output"))
      (node (ref "U8") (pin "5") (pinfunction "CKI_5") (pintype "input"))
    )
    (net (code "36") (name "Net-(U7-SDO)") (class "Default")
      (node (ref "U7") (pin "3") (pinfunction "SDO_3") (pintype "output"))
      (node (ref "U8") (pin "4") (pinfunction "SDI_4") (pintype "input"))
    )
    (net (code "37") (name "Net-(U8-CKO)") (class "Default")
      (node (ref "U8") (pin "2") (pinfunction "CKO_2") (pintype "output"))
      (node (ref "U9") (pin "5") (pinfunction "CKI_5") (pintype "input"))
    )
    (net (code "38") (name "Net-(U8-SDO)") (class "Default")
      (node (ref "U8") (pin "3") (pinfunction "SDO_3") (pintype "output"))
      (node (ref "U9") (pin "4") (pinfunction "SDI_4") (pintype "input"))
    )
    (net (code "39") (name "Net-(U10-CKI)") (class "Default")
      (node (ref "U10") (pin "5") (pinfunction "CKI_5") (pintype "input"))
      (node (ref "U9") (pin "2") (pinfunction "CKO_2") (pintype "output"))
    )
    (net (code "40") (name "Net-(U10-CKO)") (class "Default")
      (node (ref "U10") (pin "2") (pinfunction "CKO_2") (pintype "output"))
      (node (ref "U11") (pin "5") (pinfunction "CKI_5") (pintype "input"))
    )
    (net (code "41") (name "Net-(U10-SDI)") (class "Default")
      (node (ref "U10") (pin "4") (pinfunction "SDI_4") (pintype "input"))
      (node (ref "U9") (pin "3") (pinfunction "SDO_3") (pintype "output"))
    )
    (net (code "42") (name "Net-(U10-SDO)") (class "Default")
      (node (ref "U10") (pin "3") (pinfunction "SDO_3") (pintype "output"))
      (node (ref "U11") (pin "4") (pinfunction "SDI_4") (pintype "input"))
    )
    (net (code "43") (name "Net-(U11-CKO)") (class "Default")
      (node (ref "U11") (pin "2") (pinfunction "CKO_2") (pintype "output"))
      (node (ref "U12") (pin "5") (pinfunction "CKI_5") (pintype "input"))
    )
    (net (code "44") (name "Net-(U11-SDO)") (class "Default")
      (node (ref "U11") (pin "3") (pinfunction "SDO_3") (pintype "output"))
      (node (ref "U12") (pin "4") (pinfunction "SDI_4") (pintype "input"))
    )
    (net (code "45") (name "Net-(U12-CKO)") (class "Default")
      (node (ref "U12") (pin "2") (pinfunction "CKO_2") (pintype "output"))
      (node (ref "U13") (pin "5") (pinfunction "CKI_5") (pintype "input"))
    )
    (net (code "46") (name "Net-(U12-SDO)") (class "Default")
      (node (ref "U12") (pin "3") (pinfunction "SDO_3") (pintype "output"))
      (node (ref "U13") (pin "4") (pinfunction "SDI_4") (pintype "input"))
    )
    (net (code "47") (name "Net-(U13-CKO)") (class "Default")
      (node (ref "U13") (pin "2") (pinfunction "CKO_2") (pintype "output"))
      (node (ref "U14") (pin "5") (pinfunction "CKI_5") (pintype "input"))
    )
    (net (code "48") (name "Net-(U13-SDO)") (class "Default")
      (node (ref "U13") (pin "3") (pinfunction "SDO_3") (pintype "output"))
      (node (ref "U14") (pin "4") (pinfunction "SDI_4") (pintype "input"))
    )
    (net (code "49") (name "Net-(U14-CKO)") (class "Default")
      (node (ref "U14") (pin "2") (pinfunction "CKO_2") (pintype "output"))
      (node (ref "U15") (pin "5") (pinfunction "CKI_5") (pintype "input"))
    )
    (net (code "50") (name "Net-(U14-SDO)") (class "Default")
      (node (ref "U14") (pin "3") (pinfunction "SDO_3") (pintype "output"))
      (node (ref "U15") (pin "4") (pinfunction "SDI_4") (pintype "input"))
    )
    (net (code "51") (name "Net-(U15-CKO)") (class "Default")
      (node (ref "U15") (pin "2") (pinfunction "CKO_2") (pintype "output"))
      (node (ref "U17") (pin "5") (pinfunction "CKI_5") (pintype "input"))
    )
    (net (code "52") (name "Net-(U15-SDO)") (class "Default")
      (node (ref "U15") (pin "3") (pinfunction "SDO_3") (pintype "output"))
      (node (ref "U17") (pin "4") (pinfunction "SDI_4") (pintype "input"))
    )
    (net (code "53") (name "Net-(U16-CKI)") (class "Default")
      (node (ref "U16") (pin "5") (pinfunction "CKI_5") (pintype "input"))
      (node (ref "U17") (pin "2") (pinfunction "CKO_2") (pintype "output"))
    )
    (net (code "54") (name "Net-(U16-CKO)") (class "Default")
      (node (ref "U16") (pin "2") (pinfunction "CKO_2") (pintype "output"))
      (node (ref "U18") (pin "5") (pinfunction "CKI_5") (pintype "input"))
    )
    (net (code "55") (name "Net-(U16-SDI)") (class "Default")
      (node (ref "U16") (pin "4") (pinfunction "SDI_4") (pintype "input"))
      (node (ref "U17") (pin "3") (pinfunction "SDO_3") (pintype "output"))
    )
    (net (code "56") (name "Net-(U16-SDO)") (class "Default")
      (node (ref "U16") (pin "3") (pinfunction "SDO_3") (pintype "output"))
      (node (ref "U18") (pin "4") (pinfunction "SDI_4") (pintype "input"))
    )
    (net (code "57") (name "Net-(U18-CKO)") (class "Default")
      (node (ref "U18") (pin "2") (pinfunction "CKO_2") (pintype "output"))
      (node (ref "U19") (pin "5") (pinfunction "CKI_5") (pintype "input"))
    )
    (net (code "58") (name "Net-(U18-SDO)") (class "Default")
      (node (ref "U18") (pin "3") (pinfunction "SDO_3") (pintype "output"))
      (node (ref "U19") (pin "4") (pinfunction "SDI_4") (pintype "input"))
    )
    (net (code "59") (name "Net-(U19-CKO)") (class "Default")
      (node (ref "U19") (pin "2") (pinfunction "CKO_2") (pintype "output"))
      (node (ref "U20") (pin "5") (pinfunction "CKI_5") (pintype "input"))
    )
    (net (code "60") (name "Net-(U19-SDO)") (class "Default")
      (node (ref "U19") (pin "3") (pinfunction "SDO_3") (pintype "output"))
      (node (ref "U20") (pin "4") (pinfunction "SDI_4") (pintype "input"))
    )
    (net (code "61") (name "Net-(U20-CKO)") (class "Default")
      (node (ref "U20") (pin "2") (pinfunction "CKO_2") (pintype "output"))
      (node (ref "U21") (pin "5") (pinfunction "CKI_5") (pintype "input"))
    )
    (net (code "62") (name "Net-(U20-SDO)") (class "Default")
      (node (ref "U20") (pin "3") (pinfunction "SDO_3") (pintype "output"))
      (node (ref "U21") (pin "4") (pinfunction "SDI_4") (pintype "input"))
    )
    (net (code "63") (name "Net-(U21-CKO)") (class "Default")
      (node (ref "U21") (pin "2") (pinfunction "CKO_2") (pintype "output"))
      (node (ref "U22") (pin "5") (pinfunction "CKI_5") (pintype "input"))
    )
    (net (code "64") (name "Net-(U21-SDO)") (class "Default")
      (node (ref "U21") (pin "3") (pinfunction "SDO_3") (pintype "output"))
      (node (ref "U22") (pin "4") (pinfunction "SDI_4") (pintype "input"))
    )
    (net (code "65") (name "Net-(U22-CKO)") (class "Default")
      (node (ref "U22") (pin "2") (pinfunction "CKO_2") (pintype "output"))
      (node (ref "U23") (pin "5") (pinfunction "CKI_5") (pintype "input"))
    )
    (net (code "66") (name "Net-(U22-SDO)") (class "Default")
      (node (ref "U22") (pin "3") (pinfunction "SDO_3") (pintype "output"))
      (node (ref "U23") (pin "4") (pinfunction "SDI_4") (pintype "input"))
    )
    (net (code "67") (name "Net-(U23-CKO)") (class "Default")
      (node (ref "U23") (pin "2") (pinfunction "CKO_2") (pintype "output"))
      (node (ref "U24") (pin "5") (pinfunction "CKI_5") (pintype "input"))
    )
    (net (code "68") (name "Net-(U23-SDO)") (class "Default")
      (node (ref "U23") (pin "3") (pinfunction "SDO_3") (pintype "output"))
      (node (ref "U24") (pin "4") (pinfunction "SDI_4") (pintype "input"))
    )
    (net (code "69") (name "Net-(U24-CKO)") (class "Default")
      (node (ref "U24") (pin "2") (pinfunction "CKO_2") (pintype "output"))
      (node (ref "U25") (pin "5") (pinfunction "CKI_5") (pintype "input"))
    )
    (net (code "70") (name "Net-(U24-SDO)") (class "Default")
      (node (ref "U24") (pin "3") (pinfunction "SDO_3") (pintype "output"))
      (node (ref "U25") (pin "4") (pinfunction "SDI_4") (pintype "input"))
    )
    (net (code "71") (name "Net-(U25-CKO)") (class "Default")
      (node (ref "U25") (pin "2") (pinfunction "CKO_2") (pintype "output"))
      (node (ref "U26") (pin "5") (pinfunction "CKI_5") (pintype "input"))
    )
    (net (code "72") (name "Net-(U25-SDO)") (class "Default")
      (node (ref "U25") (pin "3") (pinfunction "SDO_3") (pintype "output"))
      (node (ref "U26") (pin "4") (pinfunction "SDI_4") (pintype "input"))
    )
    (net (code "73") (name "Net-(U26-CKO)") (class "Default")
      (node (ref "U26") (pin "2") (pinfunction "CKO_2") (pintype "output"))
      (node (ref "U27") (pin "5") (pinfunction "CKI_5") (pintype "input"))
    )
    (net (code "74") (name "Net-(U26-SDO)") (class "Default")
      (node (ref "U26") (pin "3") (pinfunction "SDO_3") (pintype "output"))
      (node (ref "U27") (pin "4") (pinfunction "SDI_4") (pintype "input"))
    )
    (net (code "75") (name "Net-(U27-CKO)") (class "Default")
      (node (ref "U27") (pin "2") (pinfunction "CKO_2") (pintype "output"))
      (node (ref "U28") (pin "5") (pinfunction "CKI_5") (pintype "input"))
    )
    (net (code "76") (name "Net-(U27-SDO)") (class "Default")
      (node (ref "U27") (pin "3") (pinfunction "SDO_3") (pintype "output"))
      (node (ref "U28") (pin "4") (pinfunction "SDI_4") (pintype "input"))
    )
    (net (code "77") (name "Net-(U28-CKO)") (class "Default")
      (node (ref "U28") (pin "2") (pinfunction "CKO_2") (pintype "output"))
      (node (ref "U30") (pin "5") (pinfunction "CKI_5") (pintype "input"))
    )
    (net (code "78") (name "Net-(U28-SDO)") (class "Default")
      (node (ref "U28") (pin "3") (pinfunction "SDO_3") (pintype "output"))
      (node (ref "U30") (pin "4") (pinfunction "SDI_4") (pintype "input"))
    )
    (net (code "79") (name "Net-(U29-CKI)") (class "Default")
      (node (ref "U29") (pin "5") (pinfunction "CKI_5") (pintype "input"))
      (node (ref "U30") (pin "2") (pinfunction "CKO_2") (pintype "output"))
    )
    (net (code "80") (name "Net-(U29-CKO)") (class "Default")
      (node (ref "U29") (pin "2") (pinfunction "CKO_2") (pintype "output"))
      (node (ref "U31") (pin "5") (pinfunction "CKI_5") (pintype "input"))
    )
    (net (code "81") (name "Net-(U29-SDI)") (class "Default")
      (node (ref "U29") (pin "4") (pinfunction "SDI_4") (pintype "input"))
      (node (ref "U30") (pin "3") (pinfunction "SDO_3") (pintype "output"))
    )
    (net (code "82") (name "Net-(U29-SDO)") (class "Default")
      (node (ref "U29") (pin "3") (pinfunction "SDO_3") (pintype "output"))
      (node (ref "U31") (pin "4") (pinfunction "SDI_4") (pintype "input"))
    )
    (net (code "83") (name "Net-(U31-CKO)") (class "Default")
      (node (ref "U31") (pin "2") (pinfunction "CKO_2") (pintype "output"))
      (node (ref "U32") (pin "5") (pinfunction "CKI_5") (pintype "input"))
    )
    (net (code "84") (name "Net-(U31-SDO)") (class "Default")
      (node (ref "U31") (pin "3") (pinfunction "SDO_3") (pintype "output"))
      (node (ref "U32") (pin "4") (pinfunction "SDI_4") (pintype "input"))
    )
    (net (code "85") (name "Net-(U32-CKO)") (class "Default")
      (node (ref "U32") (pin "2") (pinfunction "CKO_2") (pintype "output"))
      (node (ref "U33") (pin "5") (pinfunction "CKI_5") (pintype "input"))
    )
    (net (code "86") (name "Net-(U32-SDO)") (class "Default")
      (node (ref "U32") (pin "3") (pinfunction "SDO_3") (pintype "output"))
      (node (ref "U33") (pin "4") (pinfunction "SDI_4") (pintype "input"))
    )
    (net (code "87") (name "Net-(U33-CKO)") (class "Default")
      (node (ref "U33") (pin "2") (pinfunction "CKO_2") (pintype "output"))
      (node (ref "U34") (pin "5") (pinfunction "CKI_5") (pintype "input"))
    )
    (net (code "88") (name "Net-(U33-SDO)") (class "Default")
      (node (ref "U33") (pin "3") (pinfunction "SDO_3") (pintype "output"))
      (node (ref "U34") (pin "4") (pinfunction "SDI_4") (pintype "input"))
    )
    (net (code "89") (name "Net-(U34-CKO)") (class "Default")
      (node (ref "U34") (pin "2") (pinfunction "CKO_2") (pintype "output"))
      (node (ref "U35") (pin "5") (pinfunction "CKI_5") (pintype "input"))
    )
    (net (code "90") (name "Net-(U34-SDO)") (class "Default")
      (node (ref "U34") (pin "3") (pinfunction "SDO_3") (pintype "output"))
      (node (ref "U35") (pin "4") (pinfunction "SDI_4") (pintype "input"))
    )
    (net (code "91") (name "Net-(U35-CKO)") (class "Default")
      (node (ref "U35") (pin "2") (pinfunction "CKO_2") (pintype "output"))
      (node (ref "U36") (pin "5") (pinfunction "CKI_5") (pintype "input"))
    )
    (net (code "92") (name "Net-(U35-SDO)") (class "Default")
      (node (ref "U35") (pin "3") (pinfunction "SDO_3") (pintype "output"))
      (node (ref "U36") (pin "4") (pinfunction "SDI_4") (pintype "input"))
    )
    (net (code "93") (name "Net-(U36-CKO)") (class "Default")
      (node (ref "U36") (pin "2") (pinfunction "CKO_2") (pintype "output"))
      (node (ref "U37") (pin "5") (pinfunction "CKI_5") (pintype "input"))
    )
    (net (code "94") (name "Net-(U36-SDO)") (class "Default")
      (node (ref "U36") (pin "3") (pinfunction "SDO_3") (pintype "output"))
      (node (ref "U37") (pin "4") (pinfunction "SDI_4") (pintype "input"))
    )
    (net (code "95") (name "Net-(U37-CKO)") (class "Default")
      (node (ref "U37") (pin "2") (pinfunction "CKO_2") (pintype "output"))
      (node (ref "U38") (pin "5") (pinfunction "CKI_5") (pintype "input"))
    )
    (net (code "96") (name "Net-(U37-SDO)") (class "Default")
      (node (ref "U37") (pin "3") (pinfunction "SDO_3") (pintype "output"))
      (node (ref "U38") (pin "4") (pinfunction "SDI_4") (pintype "input"))
    )
    (net (code "97") (name "Net-(U38-CKO)") (class "Default")
      (node (ref "U38") (pin "2") (pinfunction "CKO_2") (pintype "output"))
      (node (ref "U39") (pin "5") (pinfunction "CKI_5") (pintype "input"))
    )
    (net (code "98") (name "Net-(U38-SDO)") (class "Default")
      (node (ref "U38") (pin "3") (pinfunction "SDO_3") (pintype "output"))
      (node (ref "U39") (pin "4") (pinfunction "SDI_4") (pintype "input"))
    )
    (net (code "99") (name "Net-(U39-CKO)") (class "Default")
      (node (ref "U39") (pin "2") (pinfunction "CKO_2") (pintype "output"))
      (node (ref "U40") (pin "5") (pinfunction "CKI_5") (pintype "input"))
    )
    (net (code "100") (name "Net-(U39-SDO)") (class "Default")
      (node (ref "U39") (pin "3") (pinfunction "SDO_3") (pintype "output"))
      (node (ref "U40") (pin "4") (pinfunction "SDI_4") (pintype "input"))
    )
    (net (code "101") (name "Net-(U40-CKO)") (class "Default")
      (node (ref "U40") (pin "2") (pinfunction "CKO_2") (pintype "output"))
      (node (ref "U41") (pin "5") (pinfunction "CKI_5") (pintype "input"))
    )
    (net (code "102") (name "Net-(U40-SDO)") (class "Default")
      (node (ref "U40") (pin "3") (pinfunction "SDO_3") (pintype "output"))
      (node (ref "U41") (pin "4") (pinfunction "SDI_4") (pintype "input"))
    )
    (net (code "103") (name "Net-(U41-CKO)") (class "Default")
      (node (ref "U41") (pin "2") (pinfunction "CKO_2") (pintype "output"))
      (node (ref "U43") (pin "5") (pinfunction "CKI_5") (pintype "input"))
    )
    (net (code "104") (name "Net-(U41-SDO)") (class "Default")
      (node (ref "U41") (pin "3") (pinfunction "SDO_3") (pintype "output"))
      (node (ref "U43") (pin "4") (pinfunction "SDI_4") (pintype "input"))
    )
    (net (code "105") (name "Net-(U42-CKI)") (class "Default")
      (node (ref "U42") (pin "5") (pinfunction "CKI_5") (pintype "input"))
      (node (ref "U43") (pin "2") (pinfunction "CKO_2") (pintype "output"))
    )
    (net (code "106") (name "Net-(U42-CKO)") (class "Default")
      (node (ref "U42") (pin "2") (pinfunction "CKO_2") (pintype "output"))
      (node (ref "U44") (pin "5") (pinfunction "CKI_5") (pintype "input"))
    )
    (net (code "107") (name "Net-(U42-SDI)") (class "Default")
      (node (ref "U42") (pin "4") (pinfunction "SDI_4") (pintype "input"))
      (node (ref "U43") (pin "3") (pinfunction "SDO_3") (pintype "output"))
    )
    (net (code "108") (name "Net-(U42-SDO)") (class "Default")
      (node (ref "U42") (pin "3") (pinfunction "SDO_3") (pintype "output"))
      (node (ref "U44") (pin "4") (pinfunction "SDI_4") (pintype "input"))
    )
    (net (code "109") (name "Net-(U44-CKO)") (class "Default")
      (node (ref "U44") (pin "2") (pinfunction "CKO_2") (pintype "output"))
      (node (ref "U45") (pin "5") (pinfunction "CKI_5") (pintype "input"))
    )
    (net (code "110") (name "Net-(U44-SDO)") (class "Default")
      (node (ref "U44") (pin "3") (pinfunction "SDO_3") (pintype "output"))
      (node (ref "U45") (pin "4") (pinfunction "SDI_4") (pintype "input"))
    )
    (net (code "111") (name "Net-(U45-CKO)") (class "Default")
      (node (ref "U45") (pin "2") (pinfunction "CKO_2") (pintype "output"))
      (node (ref "U46") (pin "5") (pinfunction "CKI_5") (pintype "input"))
    )
    (net (code "112") (name "Net-(U45-SDO)") (class "Default")
      (node (ref "U45") (pin "3") (pinfunction "SDO_3") (pintype "output"))
      (node (ref "U46") (pin "4") (pinfunction "SDI_4") (pintype "input"))
    )
    (net (code "113") (name "Net-(U46-CKO)") (class "Default")
      (node (ref "U46") (pin "2") (pinfunction "CKO_2") (pintype "output"))
      (node (ref "U47") (pin "5") (pinfunction "CKI_5") (pintype "input"))
    )
    (net (code "114") (name "Net-(U46-SDO)") (class "Default")
      (node (ref "U46") (pin "3") (pinfunction "SDO_3") (pintype "output"))
      (node (ref "U47") (pin "4") (pinfunction "SDI_4") (pintype "input"))
    )
    (net (code "115") (name "Net-(U47-CKO)") (class "Default")
      (node (ref "U47") (pin "2") (pinfunction "CKO_2") (pintype "output"))
      (node (ref "U48") (pin "5") (pinfunction "CKI_5") (pintype "input"))
    )
    (net (code "116") (name "Net-(U47-SDO)") (class "Default")
      (node (ref "U47") (pin "3") (pinfunction "SDO_3") (pintype "output"))
      (node (ref "U48") (pin "4") (pinfunction "SDI_4") (pintype "input"))
    )
    (net (code "117") (name "Net-(U48-CKO)") (class "Default")
      (node (ref "U48") (pin "2") (pinfunction "CKO_2") (pintype "output"))
      (node (ref "U49") (pin "5") (pinfunction "CKI_5") (pintype "input"))
    )
    (net (code "118") (name "Net-(U48-SDO)") (class "Default")
      (node (ref "U48") (pin "3") (pinfunction "SDO_3") (pintype "output"))
      (node (ref "U49") (pin "4") (pinfunction "SDI_4") (pintype "input"))
    )
    (net (code "119") (name "Net-(U49-CKO)") (class "Default")
      (node (ref "U49") (pin "2") (pinfunction "CKO_2") (pintype "output"))
      (node (ref "U50") (pin "5") (pinfunction "CKI_5") (pintype "input"))
    )
    (net (code "120") (name "Net-(U49-SDO)") (class "Default")
      (node (ref "U49") (pin "3") (pinfunction "SDO_3") (pintype "output"))
      (node (ref "U50") (pin "4") (pinfunction "SDI_4") (pintype "input"))
    )
    (net (code "121") (name "Net-(U50-CKO)") (class "Default")
      (node (ref "U50") (pin "2") (pinfunction "CKO_2") (pintype "output"))
      (node (ref "U51") (pin "5") (pinfunction "CKI_5") (pintype "input"))
    )
    (net (code "122") (name "Net-(U50-SDO)") (class "Default")
      (node (ref "U50") (pin "3") (pinfunction "SDO_3") (pintype "output"))
      (node (ref "U51") (pin "4") (pinfunction "SDI_4") (pintype "input"))
    )
    (net (code "123") (name "Net-(U51-CKO)") (class "Default")
      (node (ref "U51") (pin "2") (pinfunction "CKO_2") (pintype "output"))
      (node (ref "U52") (pin "5") (pinfunction "CKI_5") (pintype "input"))
    )
    (net (code "124") (name "Net-(U51-SDO)") (class "Default")
      (node (ref "U51") (pin "3") (pinfunction "SDO_3") (pintype "output"))
      (node (ref "U52") (pin "4") (pinfunction "SDI_4") (pintype "input"))
    )
    (net (code "125") (name "Net-(U52-CKO)") (class "Default")
      (node (ref "U52") (pin "2") (pinfunction "CKO_2") (pintype "output"))
      (node (ref "U53") (pin "5") (pinfunction "CKI_5") (pintype "input"))
    )
    (net (code "126") (name "Net-(U52-SDO)") (class "Default")
      (node (ref "U52") (pin "3") (pinfunction "SDO_3") (pintype "output"))
      (node (ref "U53") (pin "4") (pinfunction "SDI_4") (pintype "input"))
    )
    (net (code "127") (name "Net-(U53-CKO)") (class "Default")
      (node (ref "U53") (pin "2") (pinfunction "CKO_2") (pintype "output"))
      (node (ref "U54") (pin "5") (pinfunction "CKI_5") (pintype "input"))
    )
    (net (code "128") (name "Net-(U53-SDO)") (class "Default")
      (node (ref "U53") (pin "3") (pinfunction "SDO_3") (pintype "output"))
      (node (ref "U54") (pin "4") (pinfunction "SDI_4") (pintype "input"))
    )
    (net (code "129") (name "Net-(U54-CKO)") (class "Default")
      (node (ref "U54") (pin "2") (pinfunction "CKO_2") (pintype "output"))
      (node (ref "U56") (pin "5") (pinfunction "CKI_5") (pintype "input"))
    )
    (net (code "130") (name "Net-(U54-SDO)") (class "Default")
      (node (ref "U54") (pin "3") (pinfunction "SDO_3") (pintype "output"))
      (node (ref "U56") (pin "4") (pinfunction "SDI_4") (pintype "input"))
    )
    (net (code "131") (name "Net-(U55-CKI)") (class "Default")
      (node (ref "U55") (pin "5") (pinfunction "CKI_5") (pintype "input"))
      (node (ref "U56") (pin "2") (pinfunction "CKO_2") (pintype "output"))
    )
    (net (code "132") (name "Net-(U55-CKO)") (class "Default")
      (node (ref "U55") (pin "2") (pinfunction "CKO_2") (pintype "output"))
      (node (ref "U57") (pin "5") (pinfunction "CKI_5") (pintype "input"))
    )
    (net (code "133") (name "Net-(U55-SDI)") (class "Default")
      (node (ref "U55") (pin "4") (pinfunction "SDI_4") (pintype "input"))
      (node (ref "U56") (pin "3") (pinfunction "SDO_3") (pintype "output"))
    )
    (net (code "134") (name "Net-(U55-SDO)") (class "Default")
      (node (ref "U55") (pin "3") (pinfunction "SDO_3") (pintype "output"))
      (node (ref "U57") (pin "4") (pinfunction "SDI_4") (pintype "input"))
    )
    (net (code "135") (name "Net-(U57-CKO)") (class "Default")
      (node (ref "U57") (pin "2") (pinfunction "CKO_2") (pintype "output"))
      (node (ref "U58") (pin "5") (pinfunction "CKI_5") (pintype "input"))
    )
    (net (code "136") (name "Net-(U57-SDO)") (class "Default")
      (node (ref "U57") (pin "3") (pinfunction "SDO_3") (pintype "output"))
      (node (ref "U58") (pin "4") (pinfunction "SDI_4") (pintype "input"))
    )
    (net (code "137") (name "Net-(U58-CKO)") (class "Default")
      (node (ref "U58") (pin "2") (pinfunction "CKO_2") (pintype "output"))
      (node (ref "U59") (pin "5") (pinfunction "CKI_5") (pintype "input"))
    )
    (net (code "138") (name "Net-(U58-SDO)") (class "Default")
      (node (ref "U58") (pin "3") (pinfunction "SDO_3") (pintype "output"))
      (node (ref "U59") (pin "4") (pinfunction "SDI_4") (pintype "input"))
    )
    (net (code "139") (name "Net-(U59-CKO)") (class "Default")
      (node (ref "U59") (pin "2") (pinfunction "CKO_2") (pintype "output"))
      (node (ref "U60") (pin "5") (pinfunction "CKI_5") (pintype "input"))
    )
    (net (code "140") (name "Net-(U59-SDO)") (class "Default")
      (node (ref "U59") (pin "3") (pinfunction "SDO_3") (pintype "output"))
      (node (ref "U60") (pin "4") (pinfunction "SDI_4") (pintype "input"))
    )
    (net (code "141") (name "Net-(U60-CKO)") (class "Default")
      (node (ref "U60") (pin "2") (pinfunction "CKO_2") (pintype "output"))
      (node (ref "U61") (pin "5") (pinfunction "CKI_5") (pintype "input"))
    )
    (net (code "142") (name "Net-(U60-SDO)") (class "Default")
      (node (ref "U60") (pin "3") (pinfunction "SDO_3") (pintype "output"))
      (node (ref "U61") (pin "4") (pinfunction "SDI_4") (pintype "input"))
    )
    (net (code "143") (name "Net-(U61-CKO)") (class "Default")
      (node (ref "U61") (pin "2") (pinfunction "CKO_2") (pintype "output"))
      (node (ref "U62") (pin "5") (pinfunction "CKI_5") (pintype "input"))
    )
    (net (code "144") (name "Net-(U61-SDO)") (class "Default")
      (node (ref "U61") (pin "3") (pinfunction "SDO_3") (pintype "output"))
      (node (ref "U62") (pin "4") (pinfunction "SDI_4") (pintype "input"))
    )
    (net (code "145") (name "Net-(U62-CKO)") (class "Default")
      (node (ref "U62") (pin "2") (pinfunction "CKO_2") (pintype "output"))
      (node (ref "U63") (pin "5") (pinfunction "CKI_5") (pintype "input"))
    )
    (net (code "146") (name "Net-(U62-SDO)") (class "Default")
      (node (ref "U62") (pin "3") (pinfunction "SDO_3") (pintype "output"))
      (node (ref "U63") (pin "4") (pinfunction "SDI_4") (pintype "input"))
    )
    (net (code "147") (name "Net-(U63-CKO)") (class "Default")
      (node (ref "U63") (pin "2") (pinfunction "CKO_2") (pintype "output"))
      (node (ref "U64") (pin "5") (pinfunction "CKI_5") (pintype "input"))
    )
    (net (code "148") (name "Net-(U63-SDO)") (class "Default")
      (node (ref "U63") (pin "3") (pinfunction "SDO_3") (pintype "output"))
      (node (ref "U64") (pin "4") (pinfunction "SDI_4") (pintype "input"))
    )
    (net (code "149") (name "Net-(U64-CKO)") (class "Default")
      (node (ref "U64") (pin "2") (pinfunction "CKO_2") (pintype "output"))
      (node (ref "U65") (pin "5") (pinfunction "CKI_5") (pintype "input"))
    )
    (net (code "150") (name "Net-(U64-SDO)") (class "Default")
      (node (ref "U64") (pin "3") (pinfunction "SDO_3") (pintype "output"))
      (node (ref "U65") (pin "4") (pinfunction "SDI_4") (pintype "input"))
    )
    (net (code "151") (name "Net-(U65-CKO)") (class "Default")
      (node (ref "U65") (pin "2") (pinfunction "CKO_2") (pintype "output"))
      (node (ref "U66") (pin "5") (pinfunction "CKI_5") (pintype "input"))
    )
    (net (code "152") (name "Net-(U65-SDO)") (class "Default")
      (node (ref "U65") (pin "3") (pinfunction "SDO_3") (pintype "output"))
      (node (ref "U66") (pin "4") (pinfunction "SDI_4") (pintype "input"))
    )
    (net (code "153") (name "Net-(U66-CKO)") (class "Default")
      (node (ref "U66") (pin "2") (pinfunction "CKO_2") (pintype "output"))
      (node (ref "U67") (pin "5") (pinfunction "CKI_5") (pintype "input"))
    )
    (net (code "154") (name "Net-(U66-SDO)") (class "Default")
      (node (ref "U66") (pin "3") (pinfunction "SDO_3") (pintype "output"))
      (node (ref "U67") (pin "4") (pinfunction "SDI_4") (pintype "input"))
    )
    (net (code "155") (name "Net-(U67-CKO)") (class "Default")
      (node (ref "U67") (pin "2") (pinfunction "CKO_2") (pintype "output"))
      (node (ref "U69") (pin "5") (pinfunction "CKI_5") (pintype "input"))
    )
    (net (code "156") (name "Net-(U67-SDO)") (class "Default")
      (node (ref "U67") (pin "3") (pinfunction "SDO_3") (pintype "output"))
      (node (ref "U69") (pin "4") (pinfunction "SDI_4") (pintype "input"))
    )
    (net (code "157") (name "Net-(U68-CKI)") (class "Default")
      (node (ref "U68") (pin "5") (pinfunction "CKI_5") (pintype "input"))
      (node (ref "U69") (pin "2") (pinfunction "CKO_2") (pintype "output"))
    )
    (net (code "158") (name "Net-(U68-CKO)") (class "Default")
      (node (ref "U68") (pin "2") (pinfunction "CKO_2") (pintype "output"))
      (node (ref "U70") (pin "5") (pinfunction "CKI_5") (pintype "input"))
    )
    (net (code "159") (name "Net-(U68-SDI)") (class "Default")
      (node (ref "U68") (pin "4") (pinfunction "SDI_4") (pintype "input"))
      (node (ref "U69") (pin "3") (pinfunction "SDO_3") (pintype "output"))
    )
    (net (code "160") (name "Net-(U68-SDO)") (class "Default")
      (node (ref "U68") (pin "3") (pinfunction "SDO_3") (pintype "output"))
      (node (ref "U70") (pin "4") (pinfunction "SDI_4") (pintype "input"))
    )
    (net (code "161") (name "Net-(U70-CKO)") (class "Default")
      (node (ref "U70") (pin "2") (pinfunction "CKO_2") (pintype "output"))
      (node (ref "U71") (pin "5") (pinfunction "CKI_5") (pintype "input"))
    )
    (net (code "162") (name "Net-(U70-SDO)") (class "Default")
      (node (ref "U70") (pin "3") (pinfunction "SDO_3") (pintype "output"))
      (node (ref "U71") (pin "4") (pinfunction "SDI_4") (pintype "input"))
    )
    (net (code "163") (name "Net-(U71-CKO)") (class "Default")
      (node (ref "U71") (pin "2") (pinfunction "CKO_2") (pintype "output"))
      (node (ref "U72") (pin "5") (pinfunction "CKI_5") (pintype "input"))
    )
    (net (code "164") (name "Net-(U71-SDO)") (class "Default")
      (node (ref "U71") (pin "3") (pinfunction "SDO_3") (pintype "output"))
      (node (ref "U72") (pin "4") (pinfunction "SDI_4") (pintype "input"))
    )
    (net (code "165") (name "Net-(U72-CKO)") (class "Default")
      (node (ref "U72") (pin "2") (pinfunction "CKO_2") (pintype "output"))
      (node (ref "U73") (pin "5") (pinfunction "CKI_5") (pintype "input"))
    )
    (net (code "166") (name "Net-(U72-SDO)") (class "Default")
      (node (ref "U72") (pin "3") (pinfunction "SDO_3") (pintype "output"))
      (node (ref "U73") (pin "4") (pinfunction "SDI_4") (pintype "input"))
    )
    (net (code "167") (name "Net-(U73-CKO)") (class "Default")
      (node (ref "U73") (pin "2") (pinfunction "CKO_2") (pintype "output"))
      (node (ref "U74") (pin "5") (pinfunction "CKI_5") (pintype "input"))
    )
    (net (code "168") (name "Net-(U73-SDO)") (class "Default")
      (node (ref "U73") (pin "3") (pinfunction "SDO_3") (pintype "output"))
      (node (ref "U74") (pin "4") (pinfunction "SDI_4") (pintype "input"))
    )
    (net (code "169") (name "Net-(U74-CKO)") (class "Default")
      (node (ref "U74") (pin "2") (pinfunction "CKO_2") (pintype "output"))
      (node (ref "U75") (pin "5") (pinfunction "CKI_5") (pintype "input"))
    )
    (net (code "170") (name "Net-(U74-SDO)") (class "Default")
      (node (ref "U74") (pin "3") (pinfunction "SDO_3") (pintype "output"))
      (node (ref "U75") (pin "4") (pinfunction "SDI_4") (pintype "input"))
    )
    (net (code "171") (name "Net-(U75-CKO)") (class "Default")
      (node (ref "U75") (pin "2") (pinfunction "CKO_2") (pintype "output"))
      (node (ref "U76") (pin "5") (pinfunction "CKI_5") (pintype "input"))
    )
    (net (code "172") (name "Net-(U75-SDO)") (class "Default")
      (node (ref "U75") (pin "3") (pinfunction "SDO_3") (pintype "output"))
      (node (ref "U76") (pin "4") (pinfunction "SDI_4") (pintype "input"))
    )
    (net (code "173") (name "unconnected-(JP1-Pad1)") (class "Default")
      (node (ref "JP1") (pin "1") (pinfunction "1_1") (pintype "passive"))
    )
    (net (code "174") (name "unconnected-(R3-Pad1)") (class "Default")
      (node (ref "R3") (pin "1") (pinfunction "1_1") (pintype "passive"))
    )
    (net (code "175") (name "unconnected-(R4-Pad2)") (class "Default")
      (node (ref "R4") (pin "2") (pinfunction "2_2") (pintype "passive"))
    )
    (net (code "176") (name "unconnected-(R5-Pad2)") (class "Default")
      (node (ref "R5") (pin "2") (pinfunction "2_2") (pintype "passive"))
    )
    (net (code "177") (name "unconnected-(R6-Pad1)") (class "Default")
      (node (ref "R6") (pin "1") (pinfunction "1_1") (pintype "passive"))
    )
    (net (code "178") (name "unconnected-(R7-Pad2)") (class "Default")
      (node (ref "R7") (pin "2") (pinfunction "2_2") (pintype "passive"))
    )
    (net (code "179") (name "unconnected-(R8-Pad2)") (class "Default")
      (node (ref "R8") (pin "2") (pinfunction "2_2") (pintype "passive"))
    )
    (net (code "180") (name "unconnected-(R9-Pad1)") (class "Default")
      (node (ref "R9") (pin "1") (pinfunction "1_1") (pintype "passive"))
    )
    (net (code "181") (name "unconnected-(R10-Pad1)") (class "Default")
      (node (ref "R10") (pin "1") (pinfunction "1_1") (pintype "passive"))
    )
    (net (code "182") (name "unconnected-(U1-AERXD0{slash}ETXD2{slash}RPD9{slash}SDA1{slash}PMCS2{slash}PMA15{slash}RD9-Pad43)") (class "Default")
      (node (ref "U1") (pin "43") (pinfunction "AERXD0/ETXD2/RPD9/SDA1/PMCS2/PMA15/RD9_43") (pintype "bidirectional"))
    )
    (net (code "183") (name "unconnected-(U1-AERXD1{slash}ETXD3{slash}RPD0{slash}RTCC{slash}INT0{slash}RD0-Pad46)") (class "Default")
      (node (ref "U1") (pin "46") (pinfunction "AERXD1/ETXD3/RPD0/RTCC/INT0/RD0_46") (pintype "bidirectional"))
    )
    (net (code "184") (name "unconnected-(U1-AERXERR{slash}ETXCLK{slash}RPD3{slash}SCL3{slash}RD3-Pad51)") (class "Default")
      (node (ref "U1") (pin "51") (pinfunction "AERXERR/ETXCLK/RPD3/SCL3/RD3_51") (pintype "bidirectional"))
    )
    (net (code "185") (name "unconnected-(U1-AN2{slash}C2INB{slash}RPB2{slash}RB2-Pad14)") (class "Default")
      (node (ref "U1") (pin "14") (pinfunction "AN2/C2INB/RPB2/RB2_14") (pintype "bidirectional"))
    )
    (net (code "186") (name "unconnected-(U1-AN3{slash}C2INA{slash}RPB3{slash}RB3-Pad13)") (class "Default")
      (node (ref "U1") (pin "13") (pinfunction "AN3/C2INA/RPB3/RB3_13") (pintype "bidirectional"))
    )
    (net (code "187") (name "unconnected-(U1-AN4{slash}C1INB{slash}RB4-Pad12)") (class "Default")
      (node (ref "U1") (pin "12") (pinfunction "AN4/C1INB/RB4_12") (pintype "bidirectional"))
    )
    (net (code "188") (name "unconnected-(U1-AN9{slash}RPB14{slash}SCK3{slash}PMA1{slash}RB14-Pad29)") (class "Default")
      (node (ref "U1") (pin "29") (pinfunction "AN9/RPB14/SCK3/PMA1/RB14_29") (pintype "bidirectional"))
    )
    (net (code "189") (name "unconnected-(U1-AN10{slash}EMDC{slash}AEMDC{slash}RPB15{slash}OCFB{slash}PMA0{slash}RB15-Pad30)") (class "Default")
      (node (ref "U1") (pin "30") (pinfunction "AN10/EMDC/AEMDC/RPB15/OCFB/PMA0/RB15_30") (pintype "bidirectional"))
    )
    (net (code "190") (name "unconnected-(U1-AN11{slash}C2INC{slash}RPG9{slash}PMA2{slash}RG9-Pad10)") (class "Default")
      (node (ref "U1") (pin "10") (pinfunction "AN11/C2INC/RPG9/PMA2/RG9_10") (pintype "bidirectional"))
    )
    (net (code "191") (name "unconnected-(U1-AN12{slash}C2IND{slash}RPG8{slash}SCL4{slash}PMA3{slash}RG8-Pad6)") (class "Default")
      (node (ref "U1") (pin "6") (pinfunction "AN12/C2IND/RPG8/SCL4/PMA3/RG8_6") (pintype "bidirectional"))
    )
    (net (code "192") (name "unconnected-(U1-AN15{slash}ETXD1{slash}PMD7{slash}RE7-Pad3)") (class "Default")
      (node (ref "U1") (pin "3") (pinfunction "AN15/ETXD1/PMD7/RE7_3") (pintype "bidirectional"))
    )
    (net (code "193") (name "unconnected-(U1-AN16{slash}ETXD0{slash}PMD6{slash}RE6-Pad2)") (class "Default")
      (node (ref "U1") (pin "2") (pinfunction "AN16/ETXD0/PMD6/RE6_2") (pintype "bidirectional"))
    )
    (net (code "194") (name "unconnected-(U1-AN17{slash}ETXEN{slash}RPE5{slash}PMD5{slash}RE5-Pad1)") (class "Default")
      (node (ref "U1") (pin "1") (pinfunction "AN17/ETXEN/RPE5/PMD5/RE5_1") (pintype "bidirectional"))
    )
    (net (code "195") (name "unconnected-(U1-AN18{slash}ERXERR{slash}PMD4{slash}RE4-Pad64)") (class "Default")
      (node (ref "U1") (pin "64") (pinfunction "AN18/ERXERR/PMD4/RE4_64") (pintype "bidirectional"))
    )
    (net (code "196") (name "unconnected-(U1-AN45{slash}C1INA{slash}RPB5{slash}RB5-Pad11)") (class "Default")
      (node (ref "U1") (pin "11") (pinfunction "AN45/C1INA/RPB5/RB5_11") (pintype "bidirectional"))
    )
    (net (code "197") (name "unconnected-(U1-AN48{slash}RPB8{slash}PMA10{slash}RB8-Pad21)") (class "Default")
      (node (ref "U1") (pin "21") (pinfunction "AN48/RPB8/PMA10/RB8_21") (pintype "bidirectional"))
    )
    (net (code "198") (name "unconnected-(U1-AN49{slash}RPB9{slash}PMA7{slash}RB9-Pad22)") (class "Default")
      (node (ref "U1") (pin "22") (pinfunction "AN49/RPB9/PMA7/RB9_22") (pintype "bidirectional"))
    )
    (net (code "199") (name "unconnected-(U1-D+-Pad37)") (class "Default")
      (node (ref "U1") (pin "37") (pinfunction "D+_37") (pintype "bidirectional"))
    )
    (net (code "200") (name "unconnected-(U1-D--Pad36)") (class "Default")
      (node (ref "U1") (pin "36") (pinfunction "D-_36") (pintype "bidirectional"))
    )
    (net (code "201") (name "unconnected-(U1-ERXD3{slash}AETXD1{slash}RPF0{slash}RF0-Pad56)") (class "Default")
      (node (ref "U1") (pin "56") (pinfunction "ERXD3/AETXD1/RPF0/RF0_56") (pintype "bidirectional"))
    )
    (net (code "202") (name "unconnected-(U1-OSC1{slash}CLKI{slash}RC12-Pad31)") (class "Default")
      (node (ref "U1") (pin "31") (pinfunction "OSC1/CLKI/RC12_31") (pintype "bidirectional"))
    )
    (net (code "203") (name "unconnected-(U1-OSC2{slash}CLKO{slash}RC15-Pad32)") (class "Default")
      (node (ref "U1") (pin "32") (pinfunction "OSC2/CLKO/RC15_32") (pintype "bidirectional"))
    )
    (net (code "204") (name "unconnected-(U1-PGEC2{slash}AN46{slash}RPB6{slash}RB6-Pad17)") (class "Default")
      (node (ref "U1") (pin "17") (pinfunction "PGEC2/AN46/RPB6/RB6_17") (pintype "bidirectional"))
    )
    (net (code "205") (name "unconnected-(U1-PGED2{slash}AN47{slash}RPB7{slash}RB7-Pad18)") (class "Default")
      (node (ref "U1") (pin "18") (pinfunction "PGED2/AN47/RPB7/RB7_18") (pintype "bidirectional"))
    )
    (net (code "206") (name "unconnected-(U1-RPF3{slash}USBID{slash}RF3-Pad38)") (class "Default")
      (node (ref "U1") (pin "38") (pinfunction "RPF3/USBID/RF3_38") (pintype "bidirectional"))
    )
    (net (code "207") (name "unconnected-(U1-RPF4{slash}SDA5{slash}PMA9{slash}RF4-Pad41)") (class "Default")
      (node (ref "U1") (pin "41") (pinfunction "RPF4/SDA5/PMA9/RF4_41") (pintype "bidirectional"))
    )
    (net (code "208") (name "unconnected-(U1-RPF5{slash}SCL5{slash}PMA8{slash}RF5-Pad42)") (class "Default")
      (node (ref "U1") (pin "42") (pinfunction "RPF5/SCL5/PMA8/RF5_42") (pintype "bidirectional"))
    )
    (net (code "209") (name "unconnected-(U1-SOSCI{slash}RPC13{slash}RC13-Pad47)") (class "Default")
      (node (ref "U1") (pin "47") (pinfunction "SOSCI/RPC13/RC13_47") (pintype "bidirectional"))
    )
    (net (code "210") (name "unconnected-(U1-SQICS0{slash}RPD4{slash}PMWR{slash}RD4-Pad52)") (class "Default")
      (node (ref "U1") (pin "52") (pinfunction "SQICS0/RPD4/PMWR/RD4_52") (pintype "bidirectional"))
    )
    (net (code "211") (name "unconnected-(U1-SQICS1{slash}RPD5{slash}PMRD{slash}RD5-Pad53)") (class "Default")
      (node (ref "U1") (pin "53") (pinfunction "SQICS1/RPD5/PMRD/RD5_53") (pintype "bidirectional"))
    )
    (net (code "212") (name "unconnected-(U1-TCK{slash}AN7{slash}PMA11{slash}RB12-Pad27)") (class "Default")
      (node (ref "U1") (pin "27") (pinfunction "TCK/AN7/PMA11/RB12_27") (pintype "bidirectional"))
    )
    (net (code "213") (name "unconnected-(U1-TDI{slash}AN8{slash}RB13-Pad28)") (class "Default")
      (node (ref "U1") (pin "28") (pinfunction "TDI/AN8/RB13_28") (pintype "bidirectional"))
    )
    (net (code "214") (name "unconnected-(U1-TDO{slash}AN6{slash}PMA12{slash}RB11-Pad24)") (class "Default")
      (node (ref "U1") (pin "24") (pinfunction "TDO/AN6/PMA12/RB11_24") (pintype "bidirectional"))
    )
    (net (code "215") (name "unconnected-(U1-TMS{slash}CVREFOUT{slash}AN5{slash}RPB10{slash}PMA13{slash}RB10-Pad23)") (class "Default")
      (node (ref "U1") (pin "23") (pinfunction "TMS/CVREFOUT/AN5/RPB10/PMA13/RB10_23") (pintype "bidirectional"))
    )
    (net (code "216") (name "unconnected-(U1-TRCLK{slash}SQICLK{slash}ERXD2{slash}AETXD0{slash}RPF1{slash}RF1-Pad57)") (class "Default")
      (node (ref "U1") (pin "57") (pinfunction "TRCLK/SQICLK/ERXD2/AETXD0/RPF1/RF1_57") (pintype "bidirectional"))
    )
    (net (code "217") (name "unconnected-(U1-TRD0{slash}SQID0{slash}ERXD1{slash}PMD0{slash}RE0-Pad58)") (class "Default")
      (node (ref "U1") (pin "58") (pinfunction "TRD0/SQID0/ERXD1/PMD0/RE0_58") (pintype "bidirectional"))
    )
    (net (code "218") (name "unconnected-(U1-TRD1{slash}SQID1{slash}ERXD0{slash}PMD1{slash}RE1-Pad61)") (class "Default")
      (node (ref "U1") (pin "61") (pinfunction "TRD1/SQID1/ERXD0/PMD1/RE1_61") (pintype "bidirectional"))
    )
    (net (code "219") (name "unconnected-(U1-TRD2{slash}SQID2{slash}ERXDV{slash}ECRSDV{slash}AECRSDV{slash}PMD2{slash}RE2-Pad62)") (class "Default")
      (node (ref "U1") (pin "62") (pinfunction "TRD2/SQID2/ERXDV/ECRSDV/AECRSDV/PMD2/RE2_62") (pintype "bidirectional"))
    )
    (net (code "220") (name "unconnected-(U1-TRD3{slash}SQID3{slash}ERXCLK{slash}EREFCLK{slash}RPE3{slash}PMD3{slash}RE3-Pad63)") (class "Default")
      (node (ref "U1") (pin "63") (pinfunction "TRD3/SQID3/ERXCLK/EREFCLK/RPE3/PMD3/RE3_63") (pintype "bidirectional"))
    )
    (net (code "221") (name "unconnected-(U4-A0-PadP$19)") (class "Default")
      (node (ref "U4") (pin "P$19") (pinfunction "A0_P$19") (pintype "bidirectional"))
    )
    (net (code "222") (name "unconnected-(U4-ADC1-PadP$20)") (class "Default")
      (node (ref "U4") (pin "P$20") (pinfunction "ADC1_P$20") (pintype "bidirectional"))
    )
    (net (code "223") (name "unconnected-(U4-ADC2-PadP$21)") (class "Default")
      (node (ref "U4") (pin "P$21") (pinfunction "ADC2_P$21") (pintype "bidirectional"))
    )
    (net (code "224") (name "unconnected-(U4-I2C1_SCL-PadP$2)") (class "Default")
      (node (ref "U4") (pin "P$2") (pinfunction "I2C1_SCL_P$2") (pintype "bidirectional"))
    )
    (net (code "225") (name "unconnected-(U4-I2C1_SDA-PadP$1)") (class "Default")
      (node (ref "U4") (pin "P$1") (pinfunction "I2C1_SDA_P$1") (pintype "bidirectional"))
    )
    (net (code "226") (name "unconnected-(U4-I2C2_SCL-PadP$17)") (class "Default")
      (node (ref "U4") (pin "P$17") (pinfunction "I2C2_SCL_P$17") (pintype "bidirectional"))
    )
    (net (code "227") (name "unconnected-(U4-I2C2_SDA-PadP$16)") (class "Default")
      (node (ref "U4") (pin "P$16") (pinfunction "I2C2_SDA_P$16") (pintype "bidirectional"))
    )
    (net (code "228") (name "unconnected-(U4-IO14-PadP$18)") (class "Default")
      (node (ref "U4") (pin "P$18") (pinfunction "IO14_P$18") (pintype "bidirectional"))
    )
    (net (code "229") (name "unconnected-(U4-RESET-PadP$3)") (class "Default")
      (node (ref "U4") (pin "P$3") (pinfunction "RESET_P$3") (pintype "bidirectional"))
    )
    (net (code "230") (name "unconnected-(U4-SPI_CLK-PadP$15)") (class "Default")
      (node (ref "U4") (pin "P$15") (pinfunction "SPI_CLK_P$15") (pintype "bidirectional"))
    )
    (net (code "231") (name "unconnected-(U4-SPI_CS-PadP$14)") (class "Default")
      (node (ref "U4") (pin "P$14") (pinfunction "SPI_CS_P$14") (pintype "bidirectional"))
    )
    (net (code "232") (name "unconnected-(U4-SPI_IN-PadP$12)") (class "Default")
      (node (ref "U4") (pin "P$12") (pinfunction "SPI_IN_P$12") (pintype "bidirectional"))
    )
    (net (code "233") (name "unconnected-(U4-SPI_OUT-PadP$13)") (class "Default")
      (node (ref "U4") (pin "P$13") (pinfunction "SPI_OUT_P$13") (pintype "bidirectional"))
    )
    (net (code "234") (name "unconnected-(U4-SWCLK-PadP$5)") (class "Default")
      (node (ref "U4") (pin "P$5") (pinfunction "SWCLK_P$5") (pintype "bidirectional"))
    )
    (net (code "235") (name "unconnected-(U4-SWDIO-PadP$4)") (class "Default")
      (node (ref "U4") (pin "P$4") (pinfunction "SWDIO_P$4") (pintype "bidirectional"))
    )
    (net (code "236") (name "unconnected-(U4-UART_CTS-PadP$6)") (class "Default")
      (node (ref "U4") (pin "P$6") (pinfunction "UART_CTS_P$6") (pintype "bidirectional"))
    )
    (net (code "237") (name "unconnected-(U4-UART_RTS-PadP$7)") (class "Default")
      (node (ref "U4") (pin "P$7") (pinfunction "UART_RTS_P$7") (pintype "bidirectional"))
    )
    (net (code "238") (name "unconnected-(U76-CKO-Pad2)") (class "Default")
      (node (ref "U76") (pin "2") (pinfunction "CKO_2") (pintype "output"))
    )
    (net (code "239") (name "unconnected-(U76-SDO-Pad3)") (class "Default")
      (node (ref "U76") (pin "3") (pinfunction "SDO_3") (pintype "output"))
    )
  )
)
